# SCH_Quad_miner_2023-09-12.net
KiCad netlist of a schematic drawn in EasyEDA
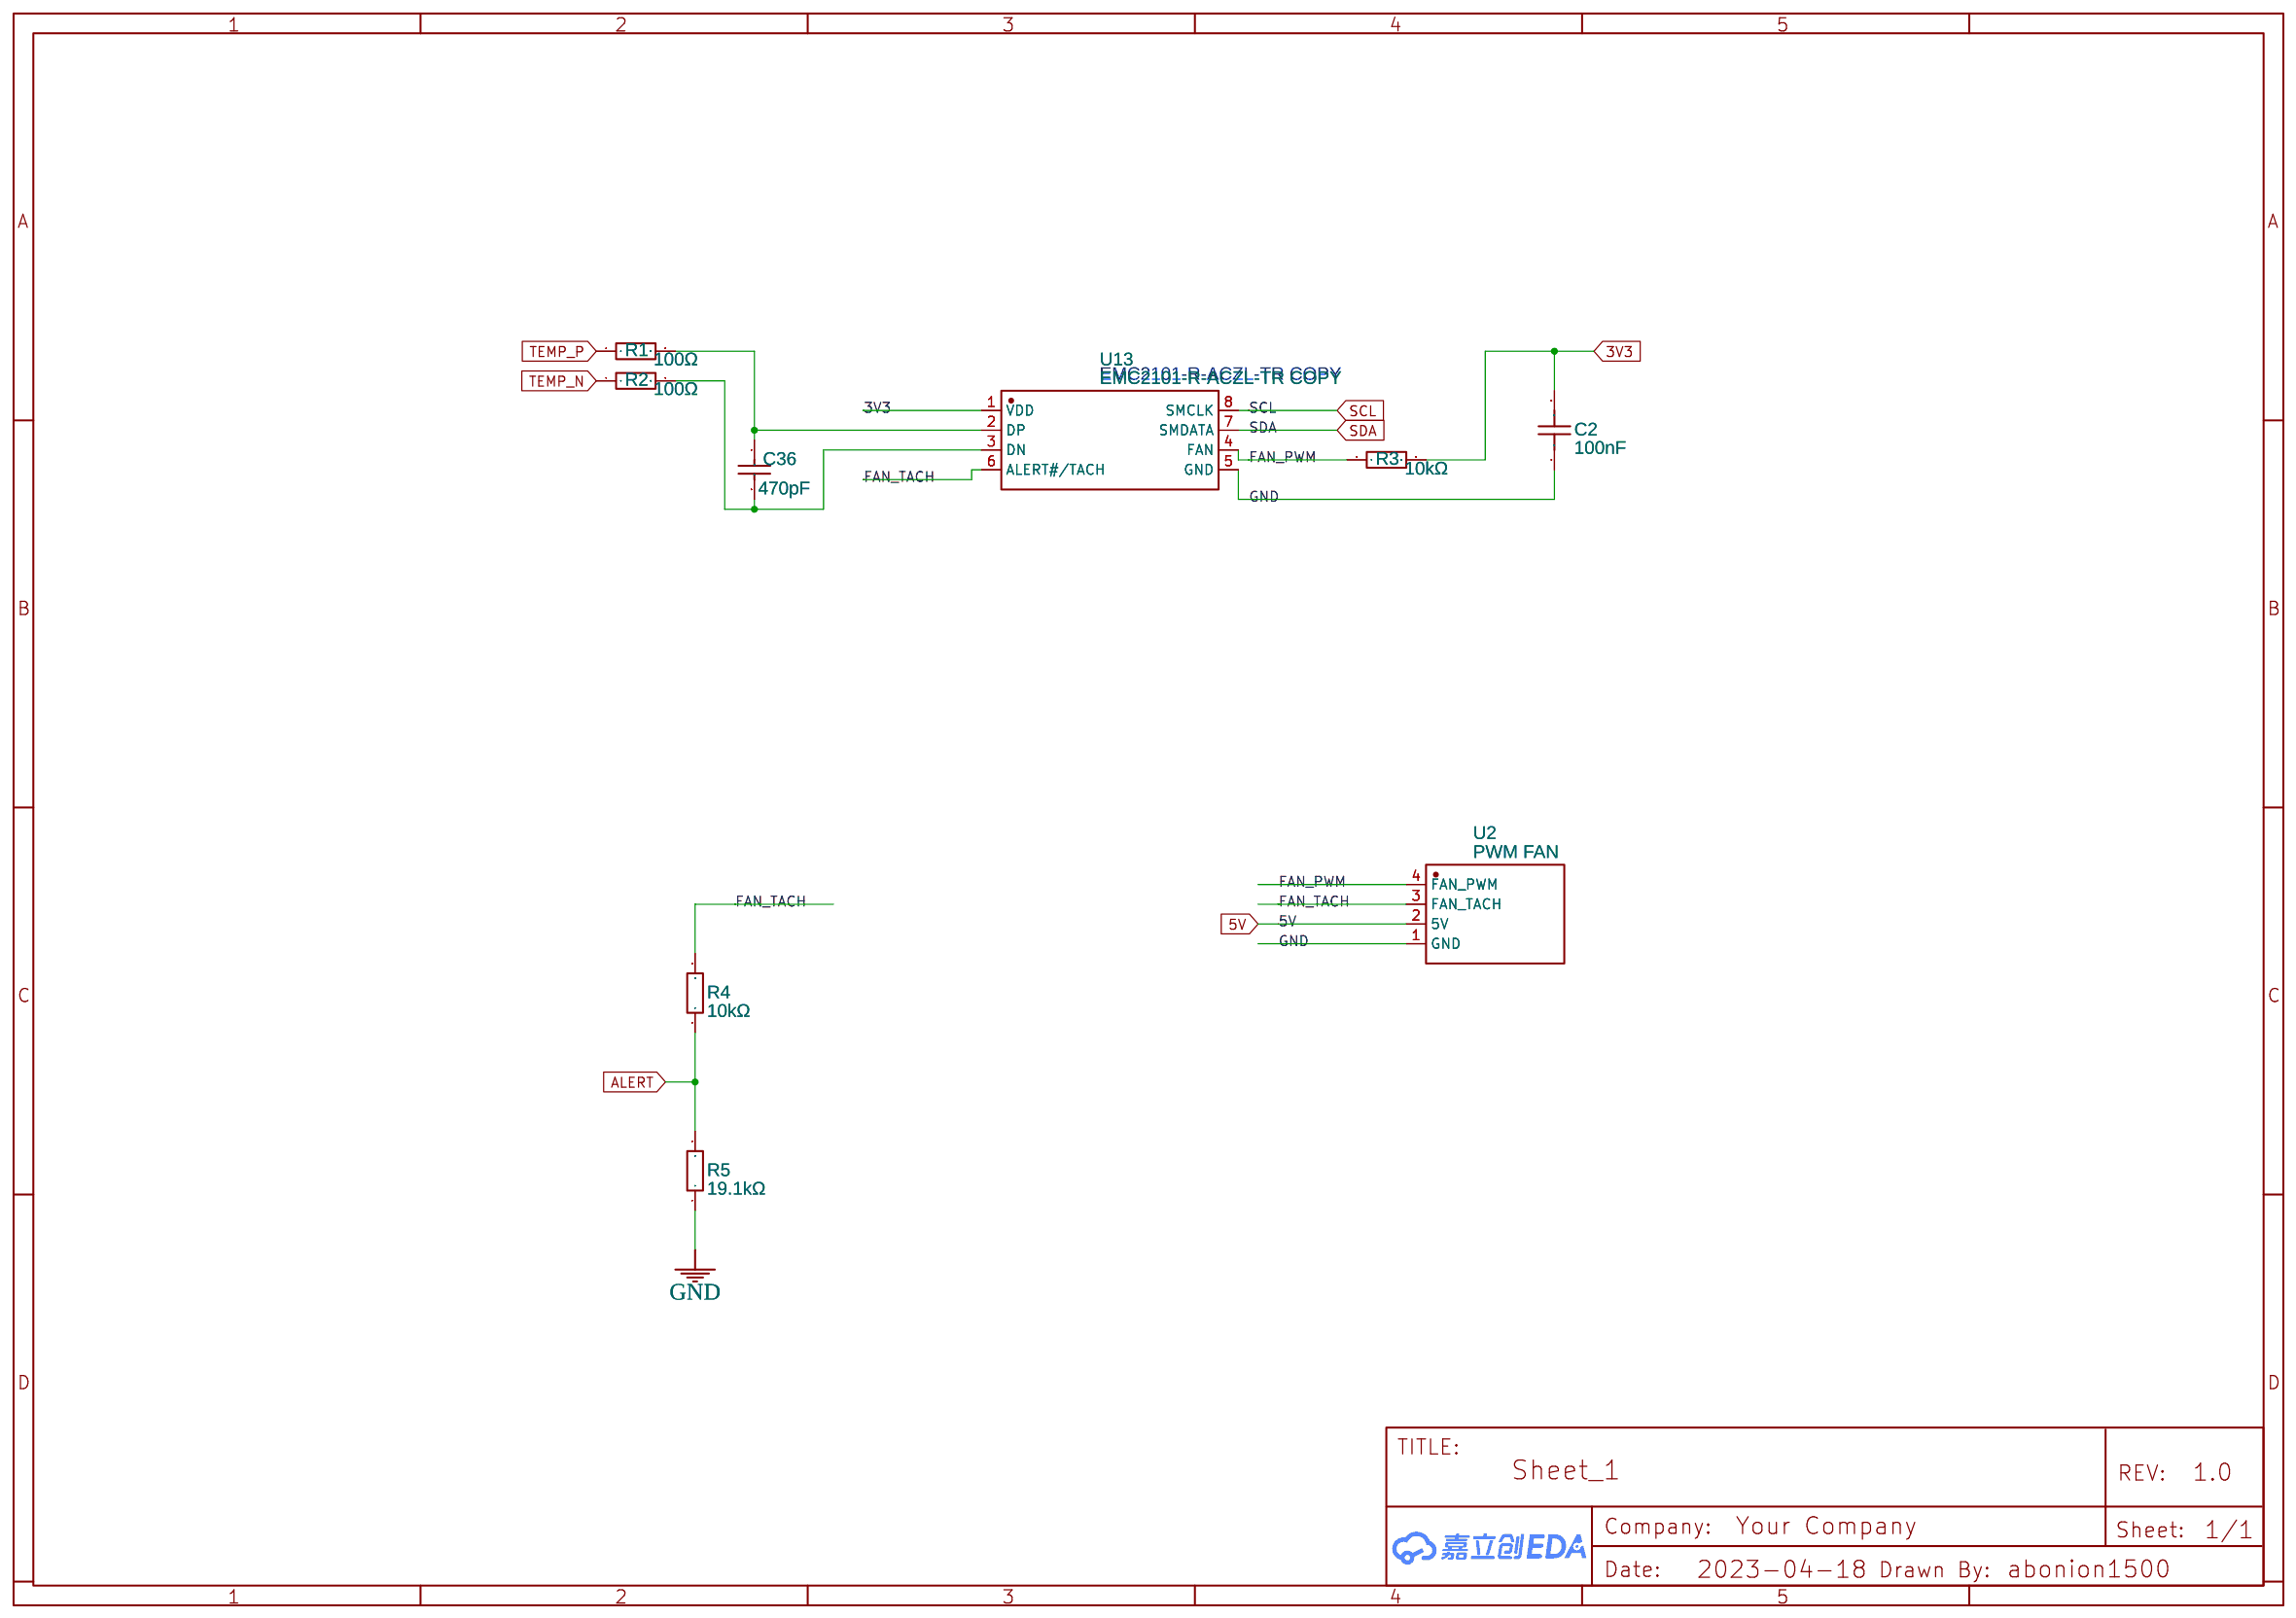
[diagram p0: EMC2101]
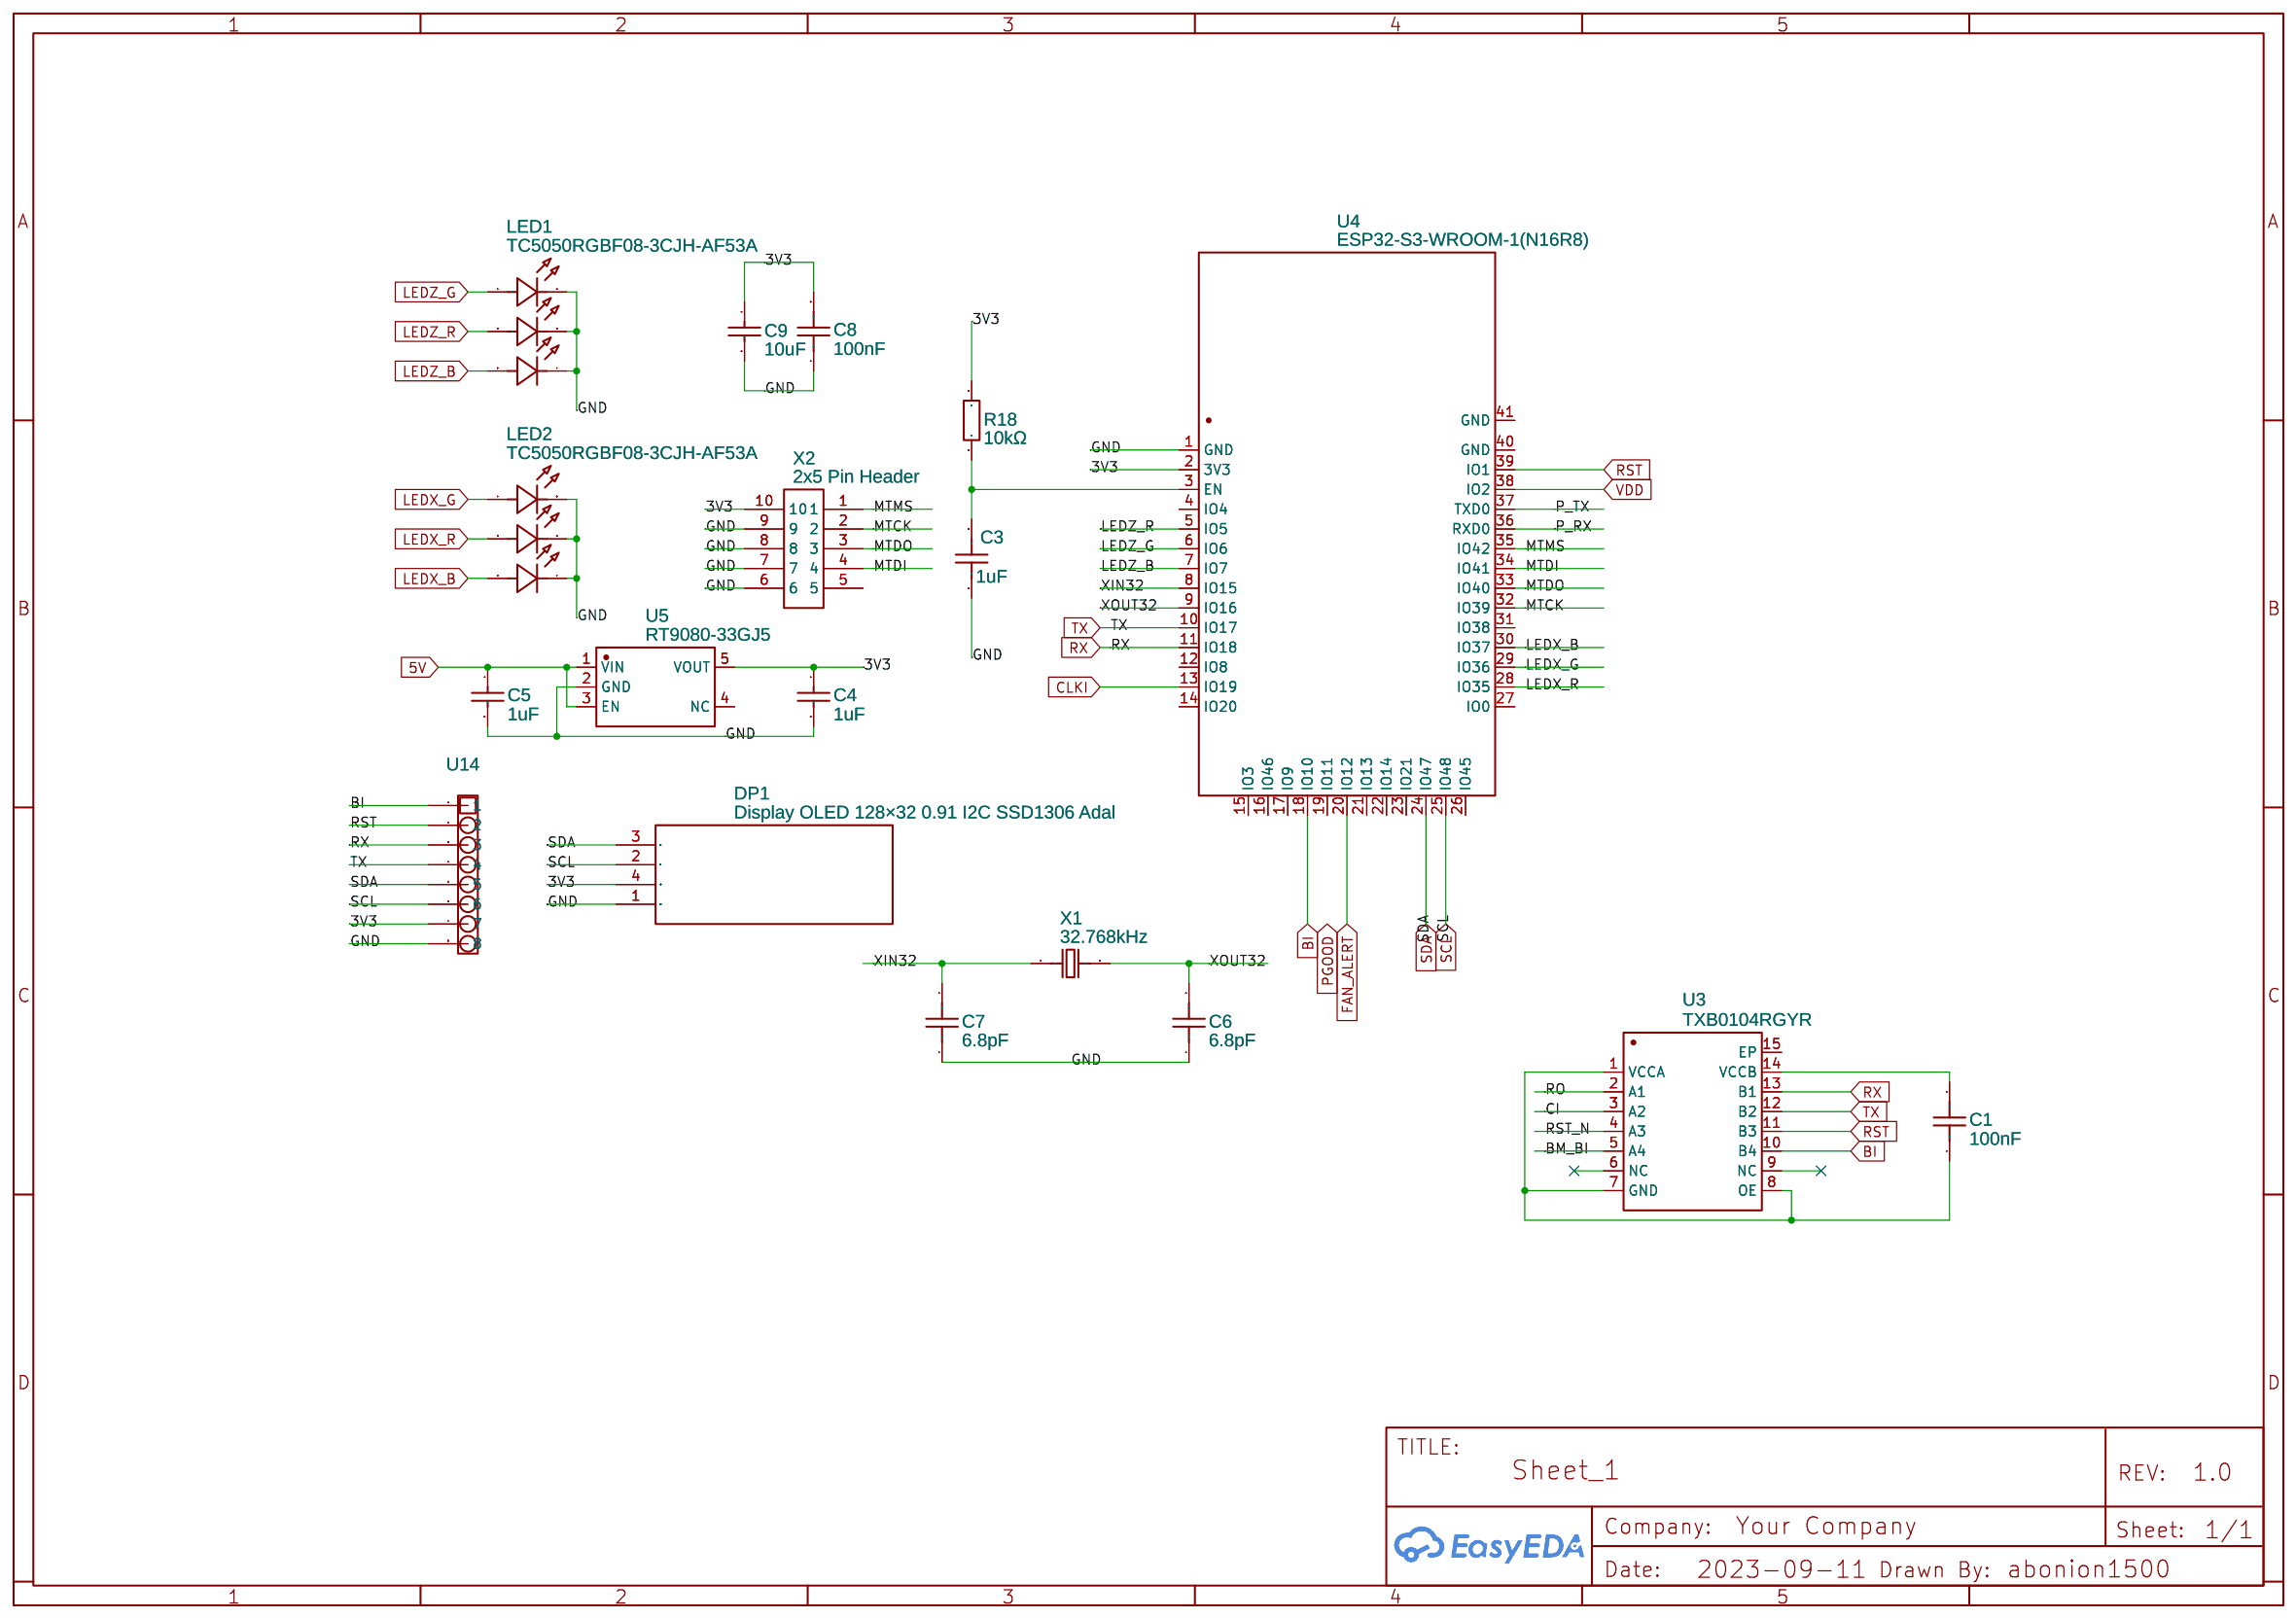
[diagram p1: Logic]
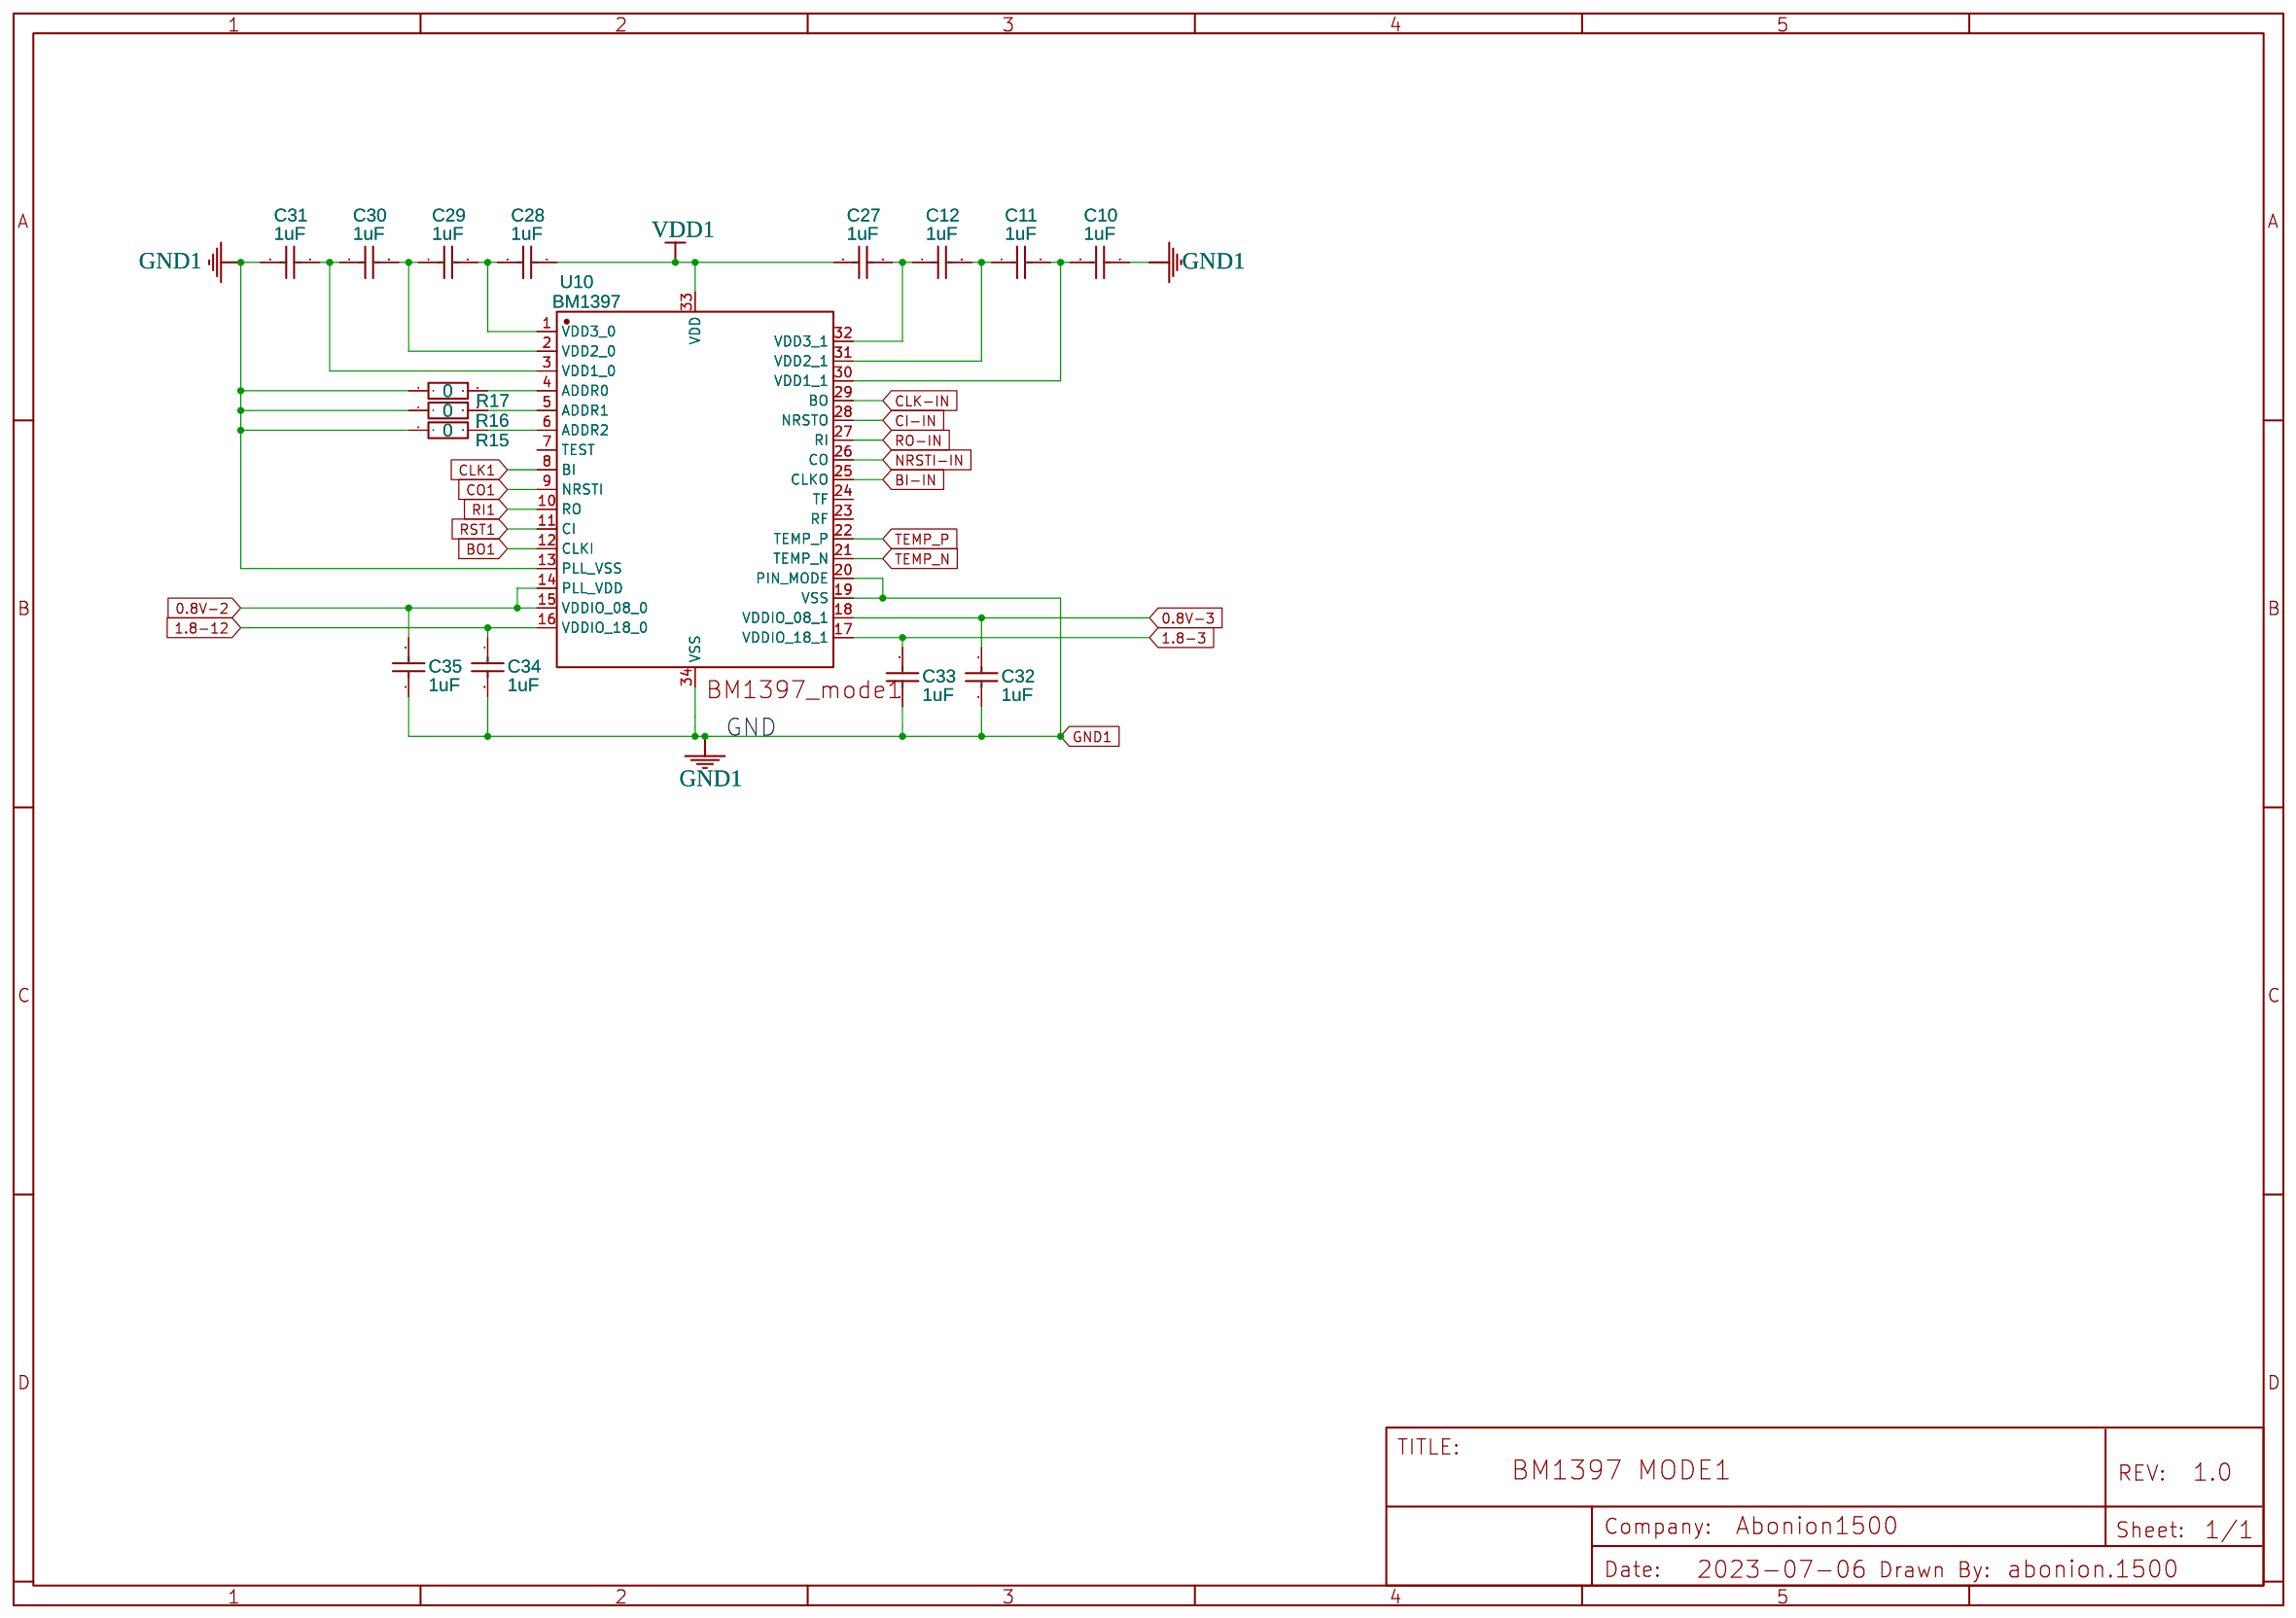
[diagram p2: Ic1]
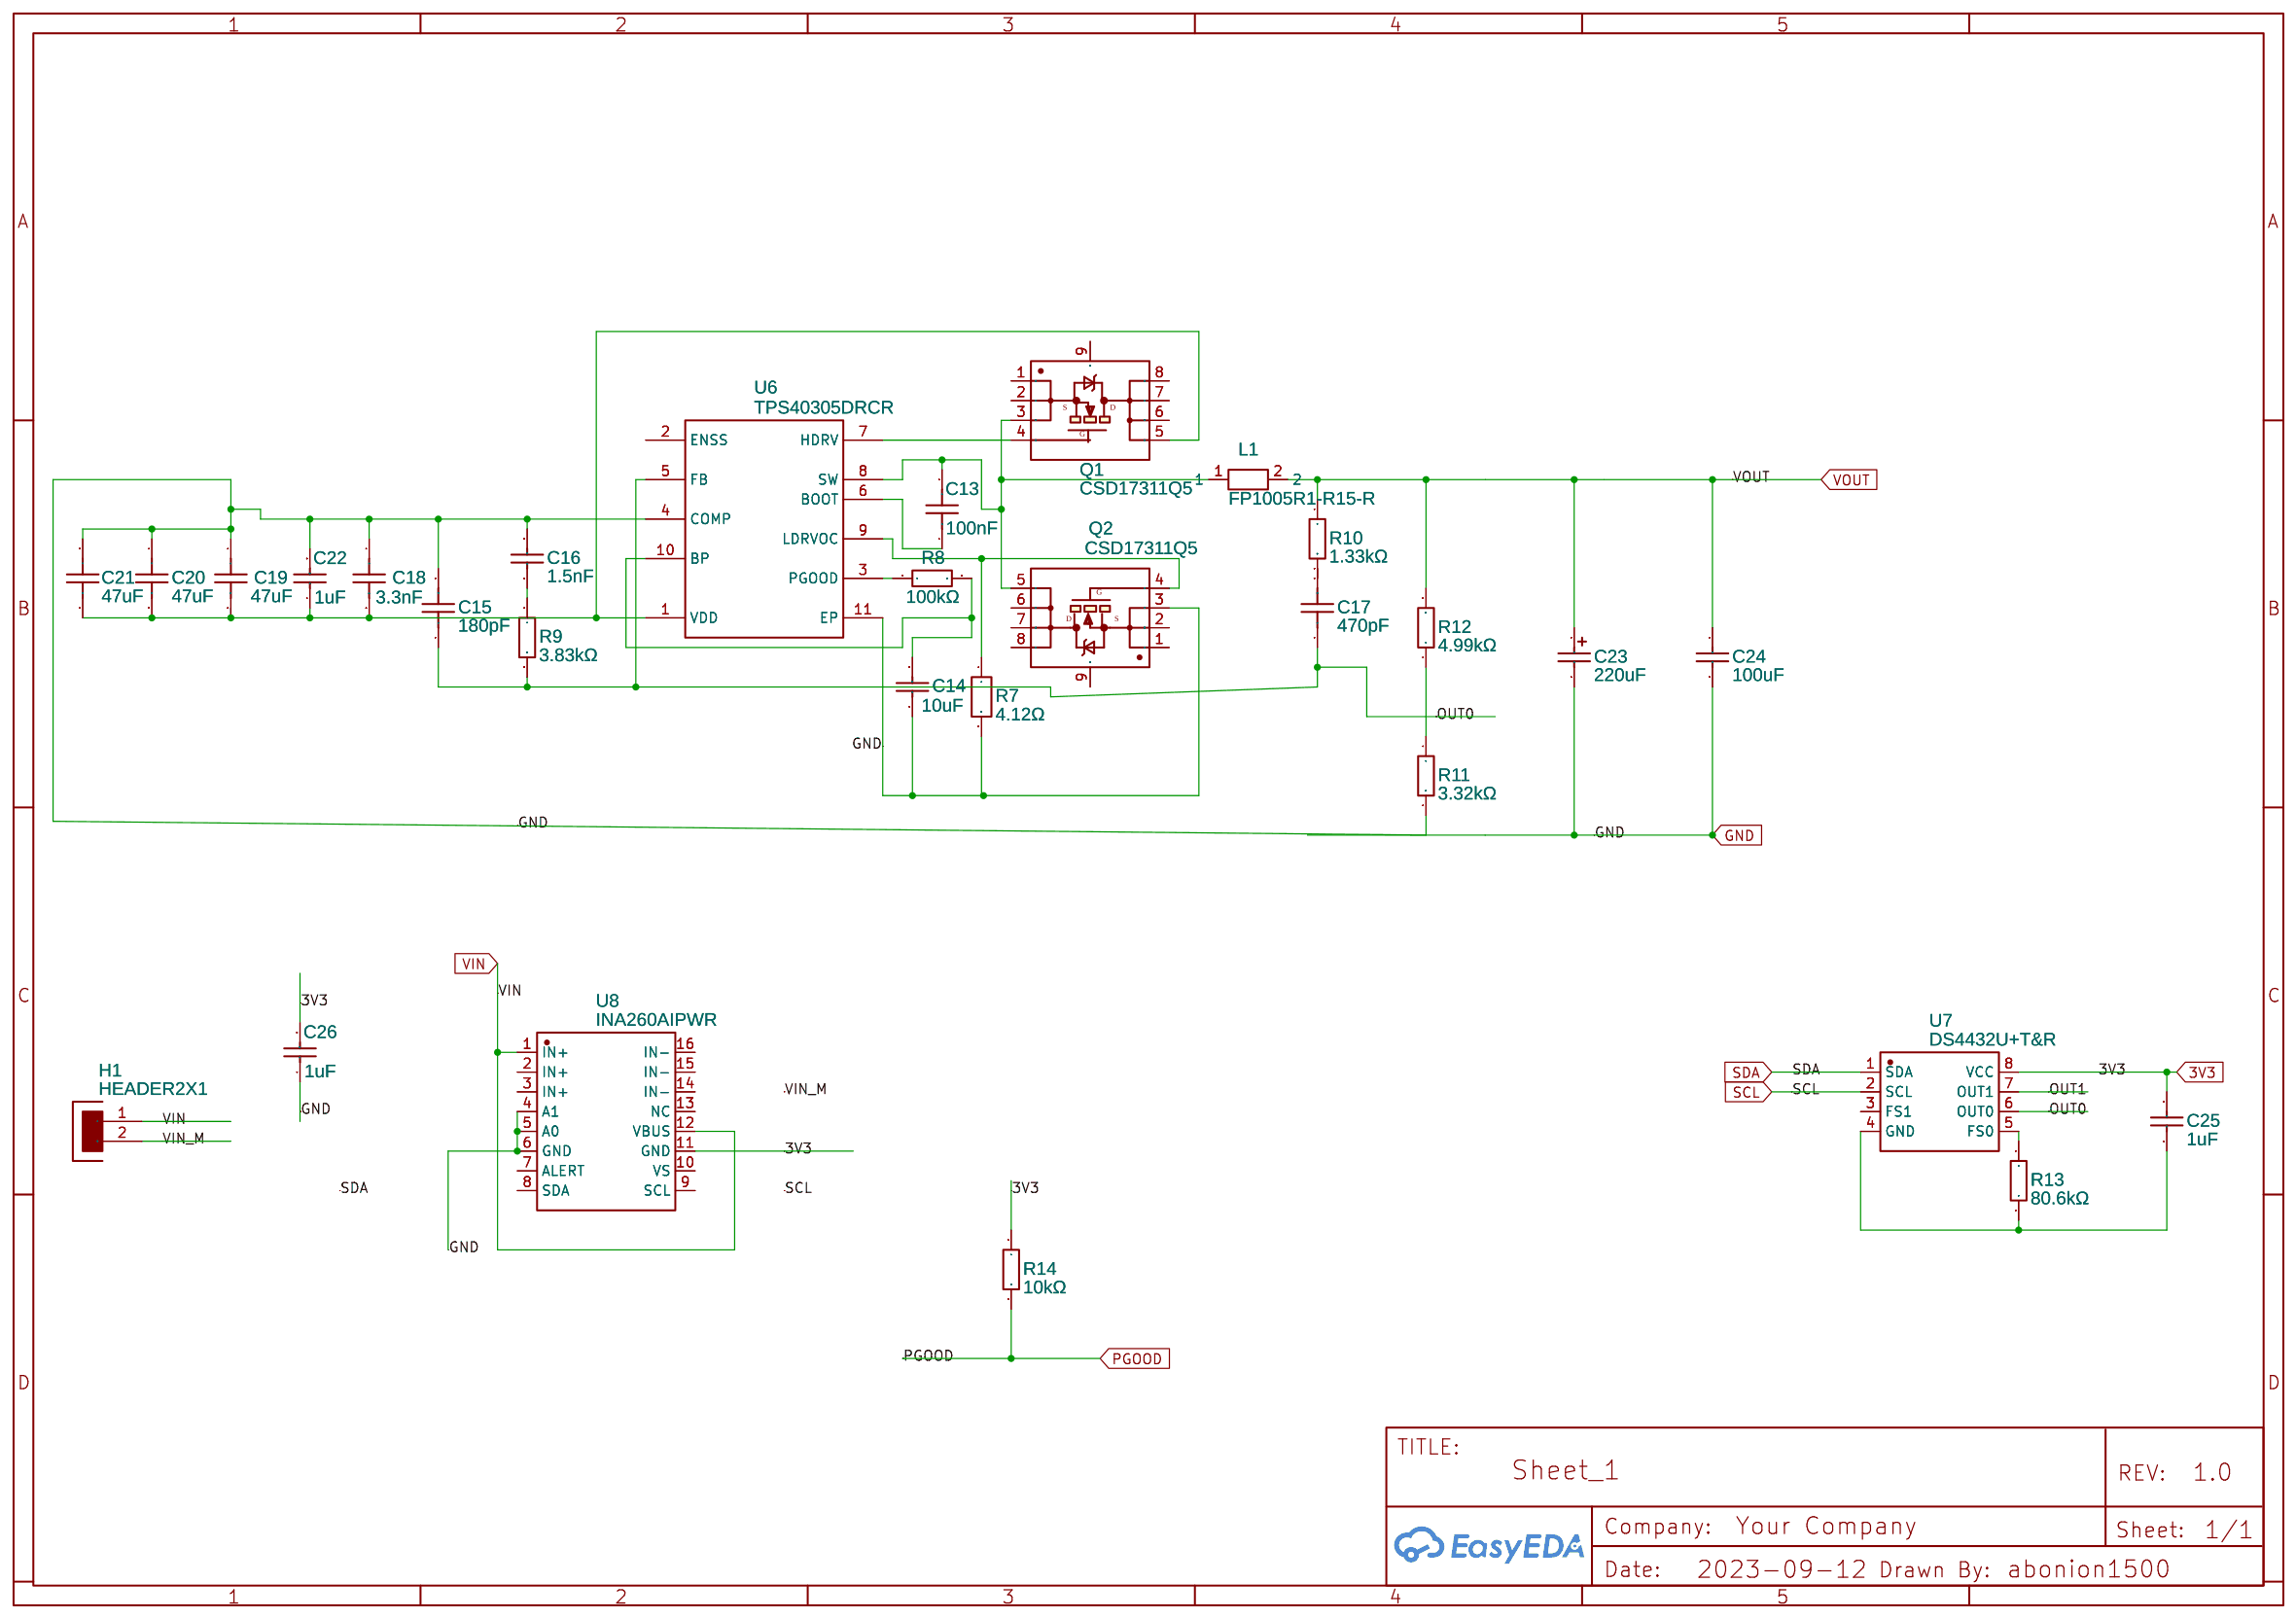
[diagram p3: Power main]
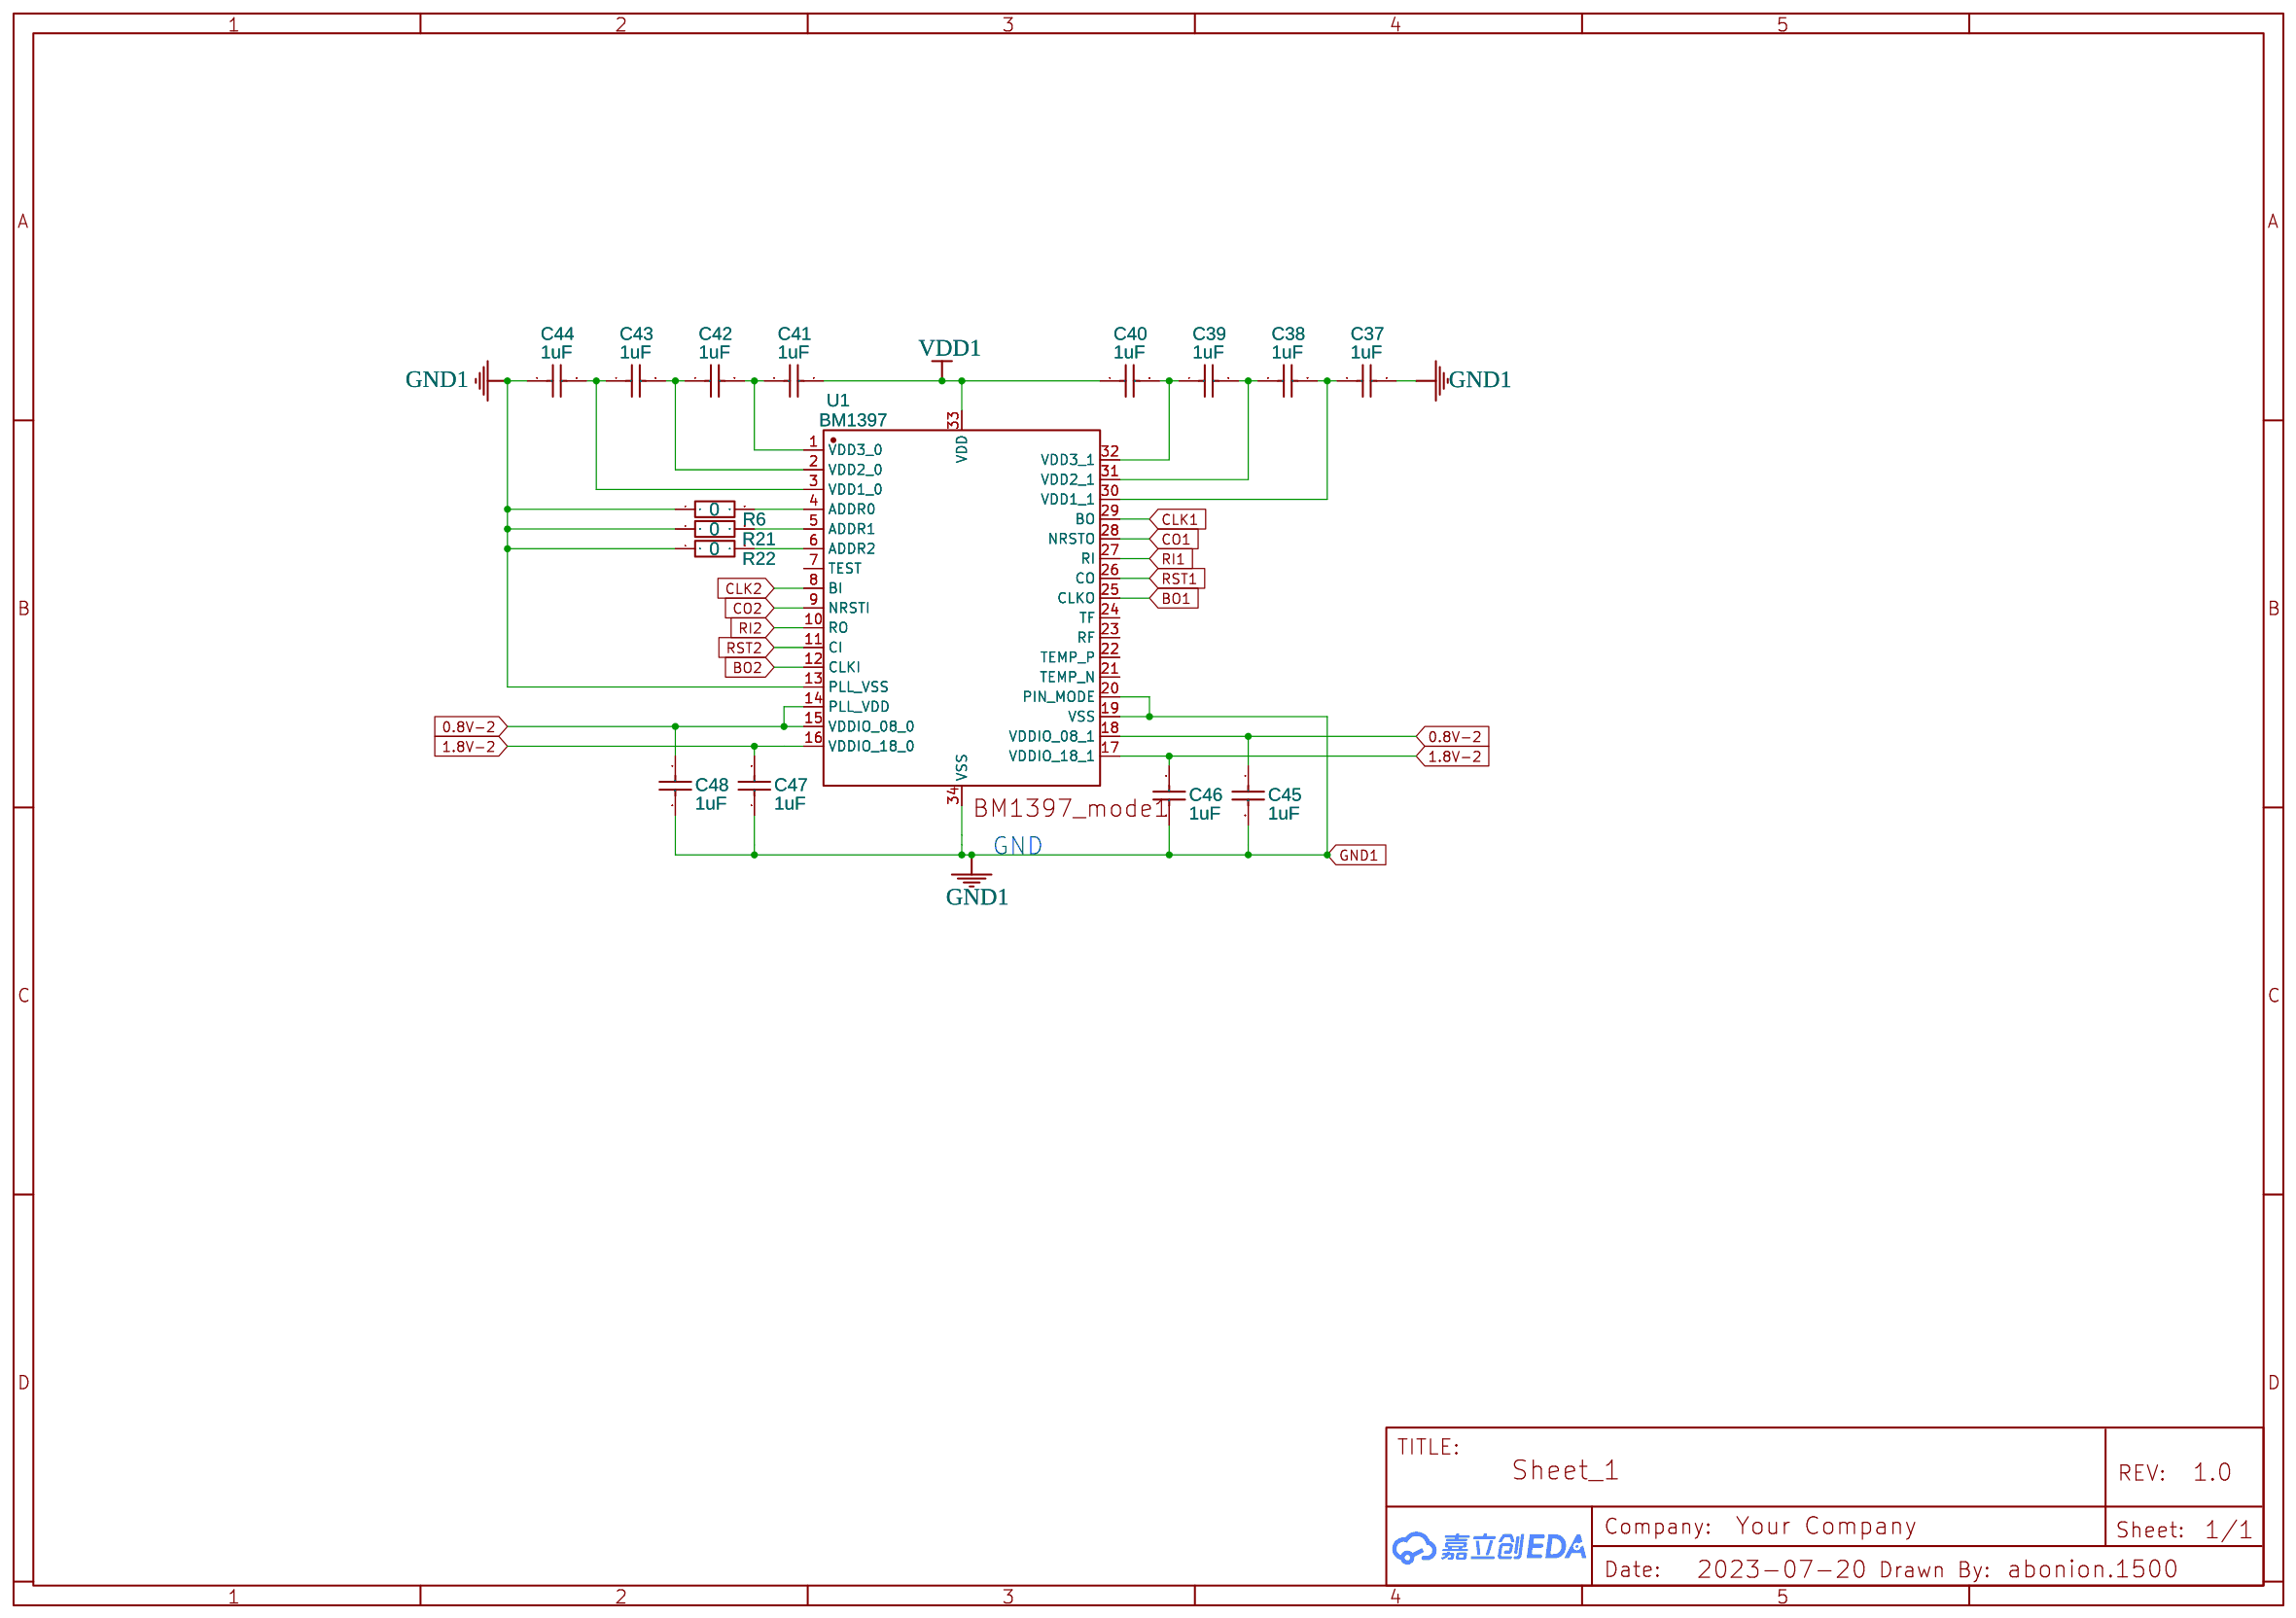
[diagram p4: Ic2]
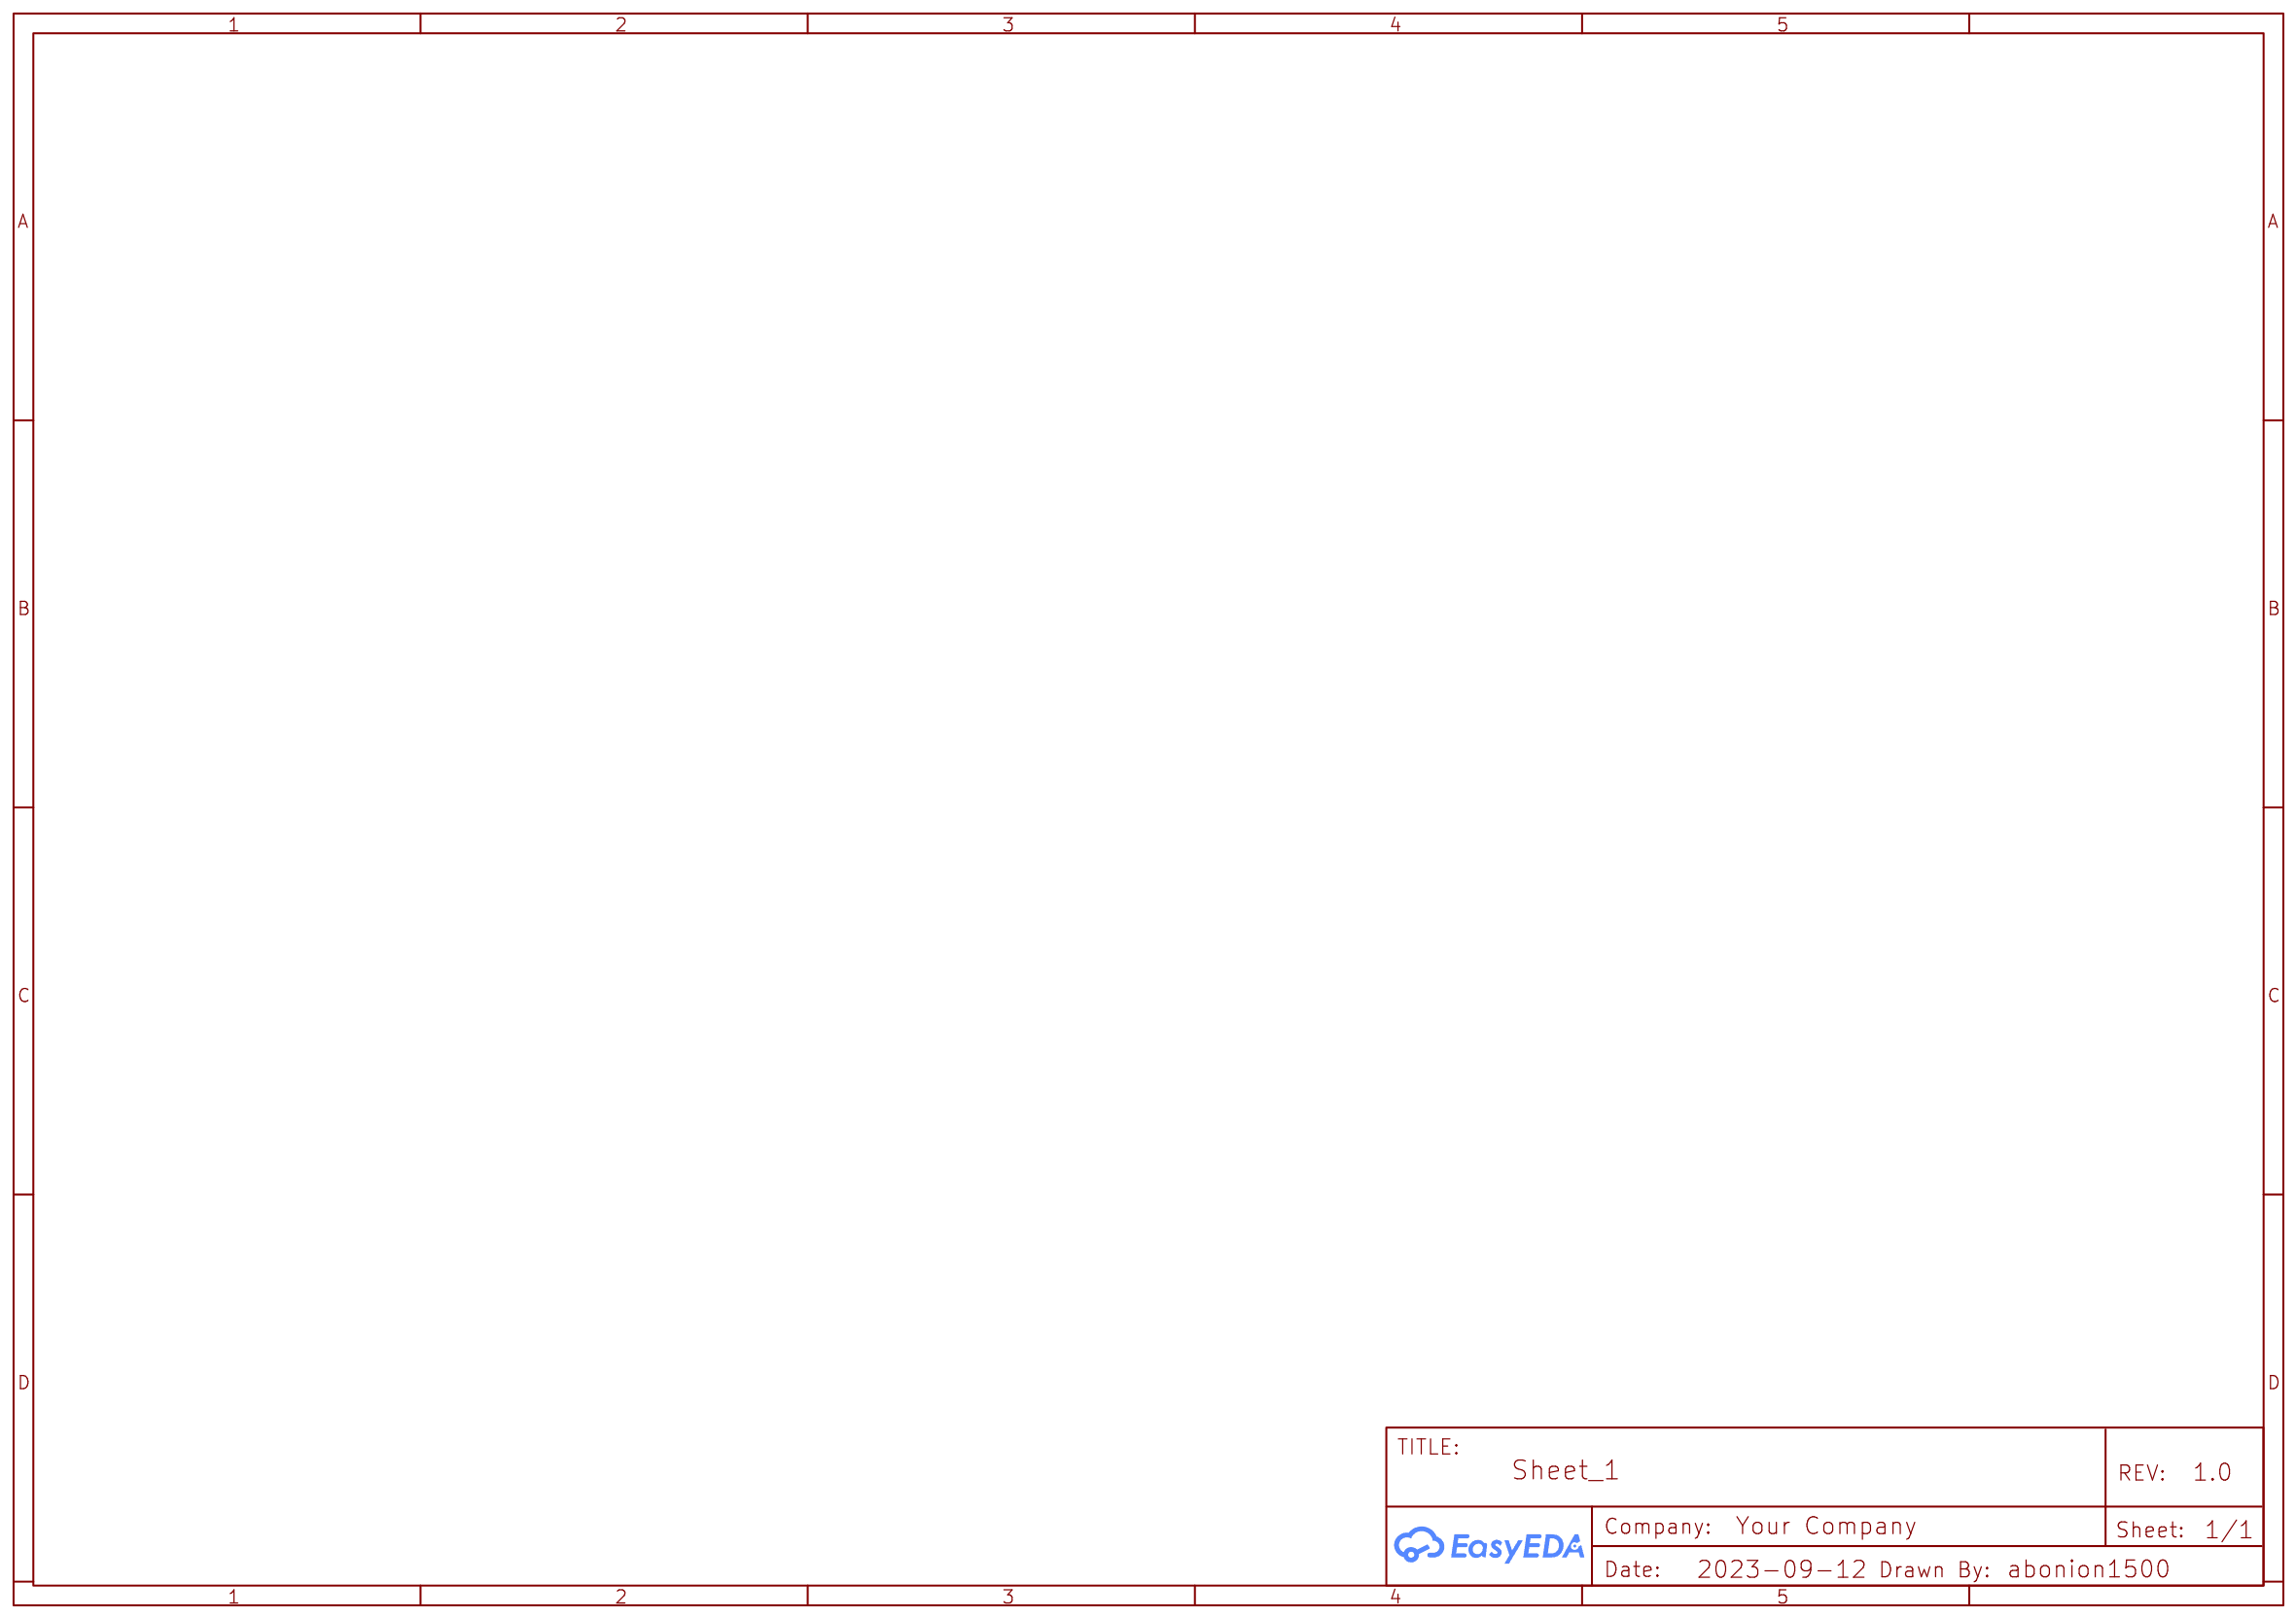
[diagram p5: Sheet_1]
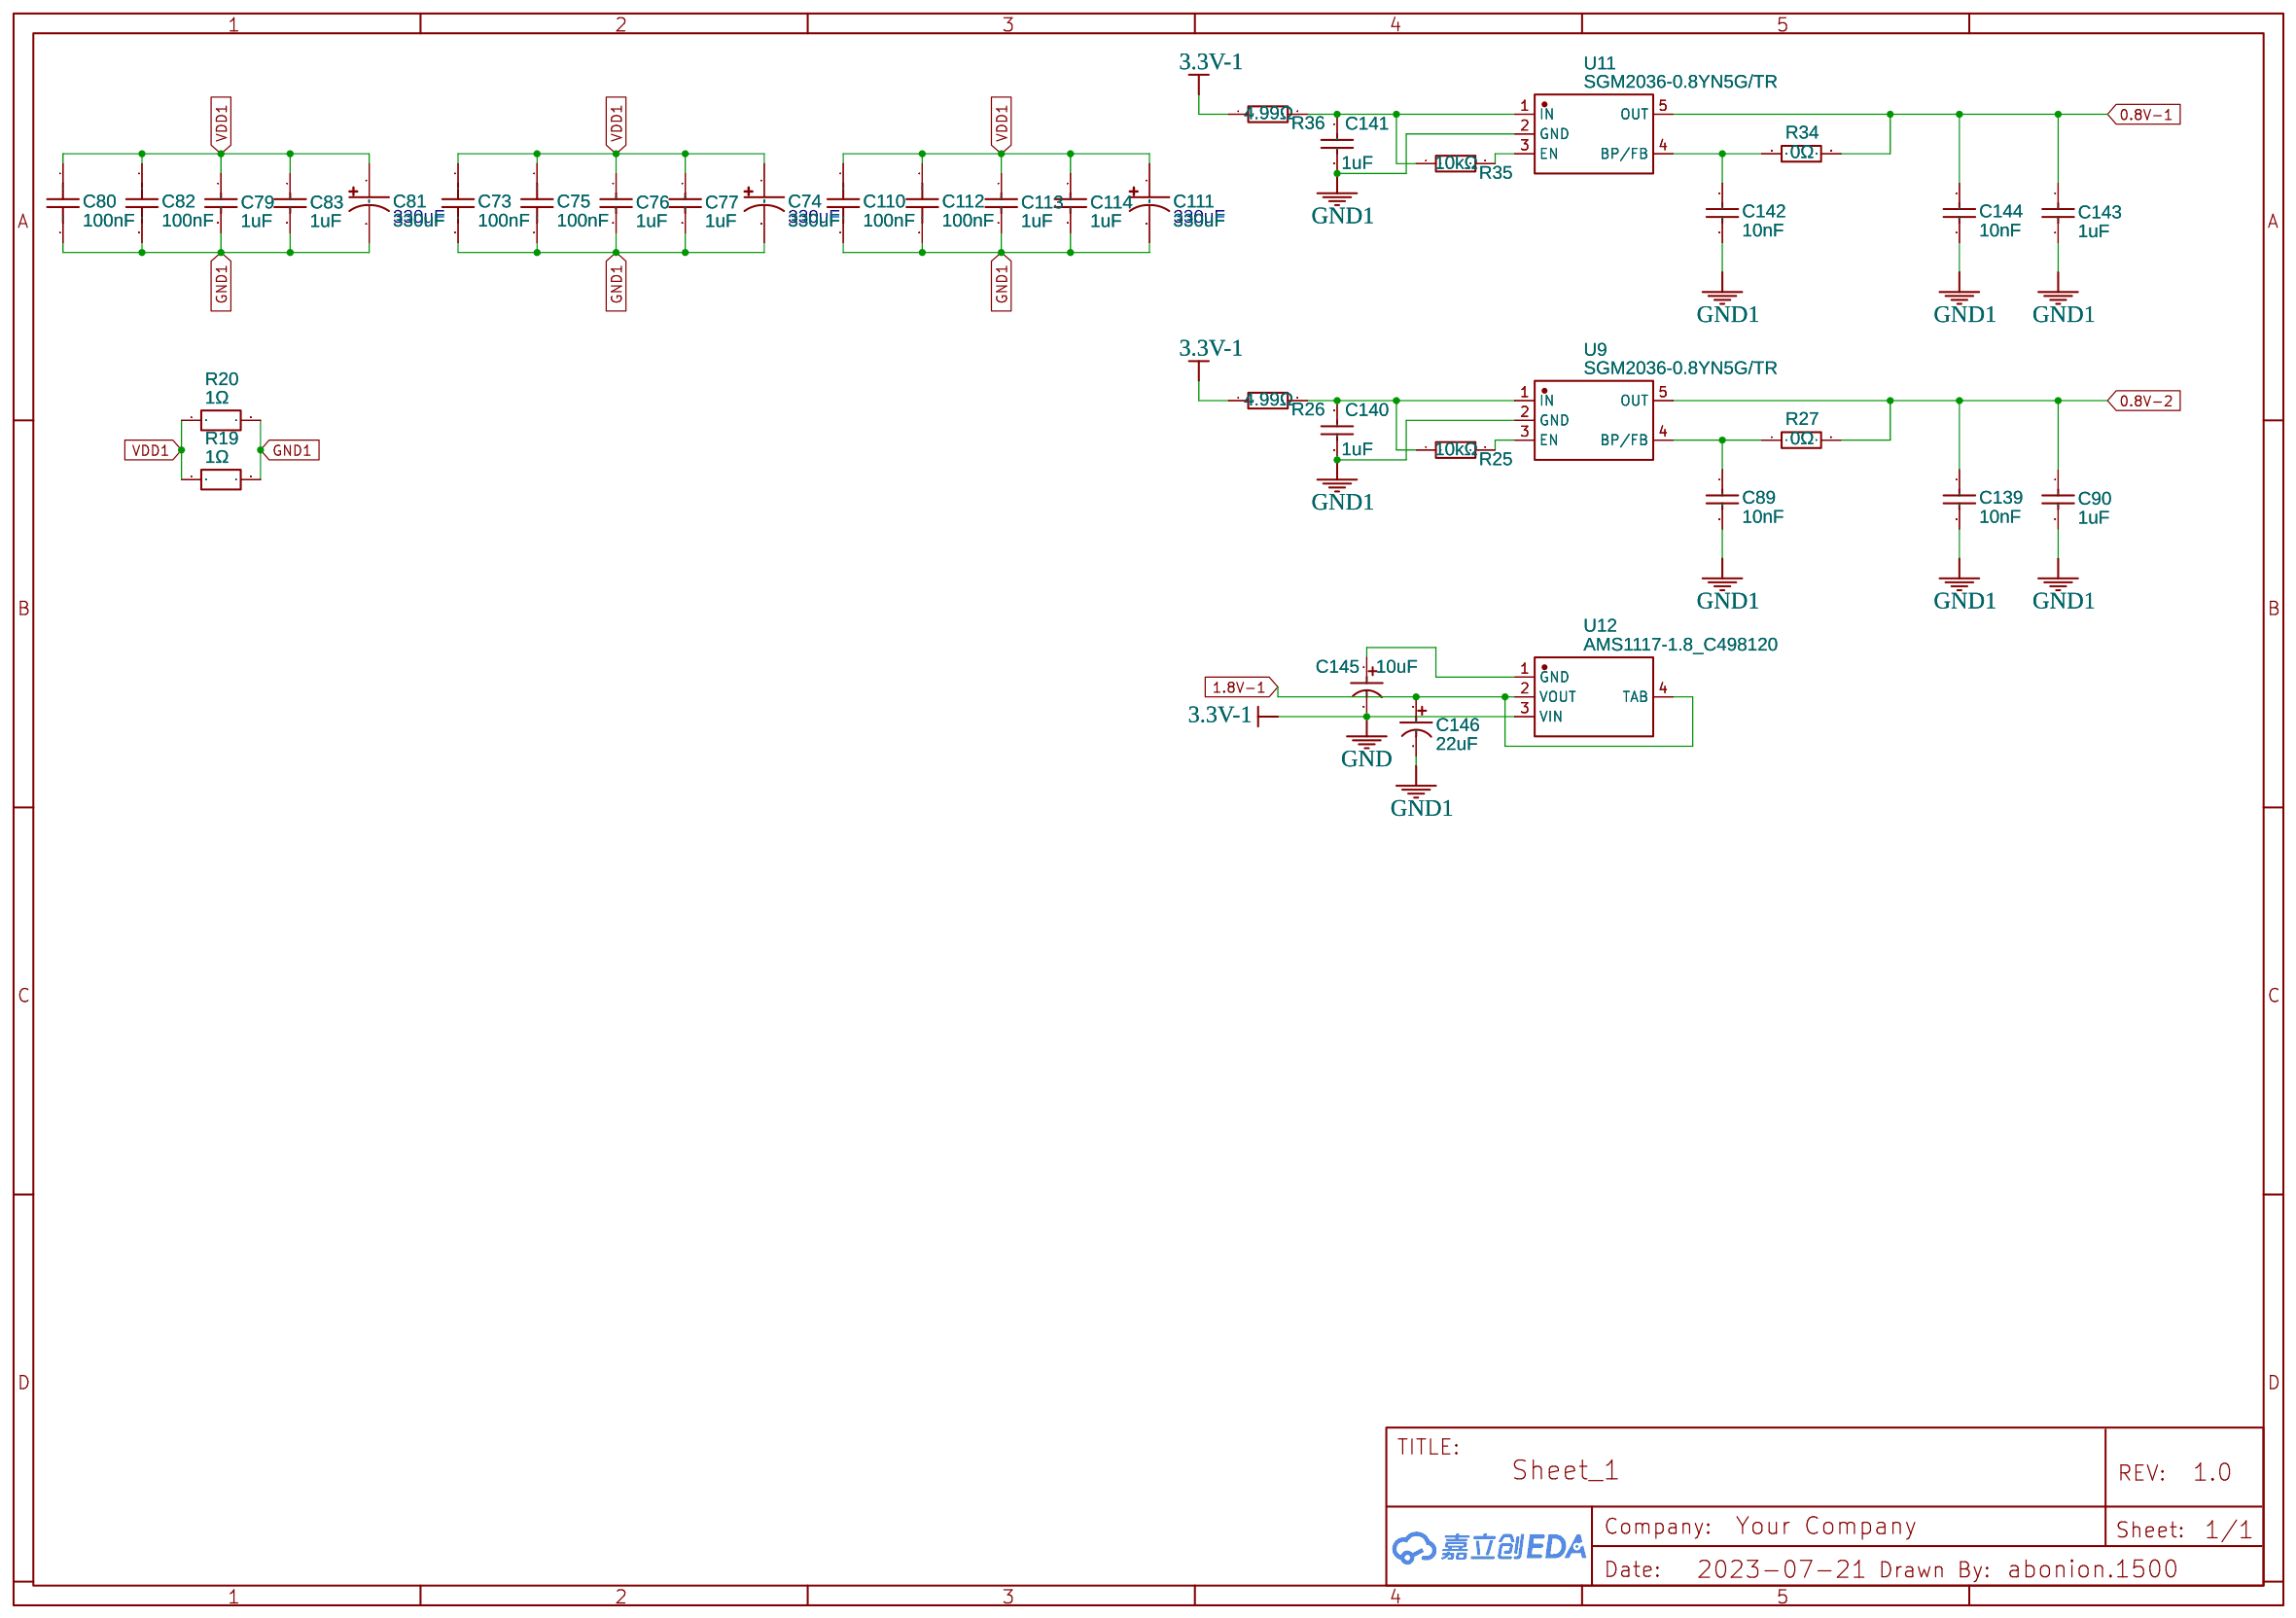
[diagram p6: Power ASICS]

(export (version "E")
  (design (tool "Eeschema 10.0.6"))
  (components
    (comp (ref "C2")
      (value "100nF")
      (fields (field (name "Manufacturer Part") "0402X104K100CT") (field (name "Manufacturer") "Walsin(华新科)"))
      (libsource (lib "") (part "0402X104K100CT"))
    )
    (comp (ref "C36")
      (value "470pF")
      (fields
        (field (name "Manufacturer Part") "CL05B471KB5NNNC")
        (field (name "Manufacturer") "SAMSUNG(三星)")
      )
      (libsource (lib "") (part "CL05B471KB5NNNC"))
    )
    (comp (ref "R1")
      (value "100Ω")
      (fields
        (field (name "Manufacturer Part") "RMCF0402FT100R")
        (field (name "Manufacturer") "SEI(Stackpole Electronics Inc.)")
      )
      (libsource (lib "") (part "RMCF0402FT100R"))
    )
    (comp (ref "R2")
      (value "100Ω")
      (fields
        (field (name "Manufacturer Part") "RMCF0402FT100R")
        (field (name "Manufacturer") "SEI(Stackpole Electronics Inc.)")
      )
      (libsource (lib "") (part "RMCF0402FT100R"))
    )
    (comp (ref "R3")
      (value "10kΩ")
      (fields (field (name "Manufacturer Part") "RC0402JR-0710KL") (field (name "Manufacturer") "YAGEO(国巨)"))
      (libsource (lib "") (part "RC0402JR-0710KL"))
    )
    (comp (ref "R4")
      (value "10kΩ")
      (fields (field (name "Manufacturer Part") "RC-02W103JT") (field (name "Manufacturer") "FH(风华)"))
      (libsource (lib "") (part "RC-02W103JT_C140214"))
    )
    (comp (ref "R5")
      (value "19.1kΩ")
      (fields
        (field (name "Manufacturer Part") "0402WGF1912TCE")
        (field (name "Manufacturer") "UNI-ROYAL(厚声)")
      )
      (libsource (lib "") (part "0402WGF1912TCE"))
    )
    (comp (ref "U2") (value "PWM FAN") (libsource (lib "") (part "PWM FAN")))
    (comp (ref "U13")
      (value "EMC2101-R-ACZL-TR COPY")
      (fields
        (field (name "Manufacturer Part") "EMC2101-R-ACZL-TR")
        (field (name "Manufacturer") "MICROCHIP(美国微芯)")
      )
      (libsource (lib "") (part "EMC2101-R-ACZL-TR COPY"))
    )
    (comp (ref "C1")
      (value "100nF")
      (fields (field (name "Manufacturer Part") "0402X104K100CT") (field (name "Manufacturer") "Walsin(华新科)"))
      (libsource (lib "") (part "0402X104K100CT"))
    )
    (comp (ref "C3")
      (value "1uF")
      (fields (field (name "Manufacturer Part") "0603X105J160CT") (field (name "Manufacturer") "Walsin(华新科)"))
      (libsource (lib "") (part "0603X105J160CT"))
    )
    (comp (ref "C4")
      (value "1uF")
      (fields
        (field (name "Manufacturer Part") "CL05A105KO5NNNC")
        (field (name "Manufacturer") "SAMSUNG(三星)")
      )
      (libsource (lib "") (part "CL05A105KO5NNNC"))
    )
    (comp (ref "C5")
      (value "1uF")
      (fields
        (field (name "Manufacturer Part") "CL05A105KO5NNNC")
        (field (name "Manufacturer") "SAMSUNG(三星)")
      )
      (libsource (lib "") (part "CL05A105KO5NNNC"))
    )
    (comp (ref "C6")
      (value "6.8pF")
      (fields (field (name "Manufacturer Part") "C1005NP0689DGT") (field (name "Manufacturer") "DARFON(达方)"))
      (libsource (lib "") (part "C1005NPO689DGT"))
    )
    (comp (ref "C7")
      (value "6.8pF")
      (fields (field (name "Manufacturer Part") "C1005NP0689DGT") (field (name "Manufacturer") "DARFON(达方)"))
      (libsource (lib "") (part "C1005NPO689DGT"))
    )
    (comp (ref "C8")
      (value "100nF")
      (fields (field (name "Manufacturer Part") "0402X104K100CT") (field (name "Manufacturer") "Walsin(华新科)"))
      (libsource (lib "") (part "0402X104K100CT"))
    )
    (comp (ref "C9")
      (value "10uF")
      (fields
        (field (name "Manufacturer Part") "CL21A106KOQNNNE")
        (field (name "Manufacturer") "SAMSUNG(三星)")
      )
      (libsource (lib "") (part "CL21A106KOQNNNE"))
    )
    (comp (ref "DP1")
      (value "Display OLED 128×32 0.91 I2C SSD1306 Adal")
      (libsource (lib "") (part "Display OLED 128×32 0.91 I2C SSD1306 Adal"))
    )
    (comp (ref "LED1")
      (value "TC5050RGBF08-3CJH-AF53A")
      (fields (field (name "Manufacturer") "TCWIN(天成)"))
      (libsource (lib "") (part "TC5050RGBF08-3CJH-AF53A"))
    )
    (comp (ref "LED2")
      (value "TC5050RGBF08-3CJH-AF53A")
      (fields (field (name "Manufacturer") "TCWIN(天成)"))
      (libsource (lib "") (part "TC5050RGBF08-3CJH-AF53A"))
    )
    (comp (ref "R18")
      (value "10kΩ")
      (fields (field (name "Manufacturer Part") "RC0402JR-0710KL") (field (name "Manufacturer") "YAGEO(国巨)"))
      (libsource (lib "") (part "RC0402JR-0710KL"))
    )
    (comp (ref "U3")
      (value "TXB0104RGYR")
      (fields (field (name "Manufacturer") "TI(德州仪器)"))
      (libsource (lib "") (part "TXB0104RGYR"))
    )
    (comp (ref "U4")
      (value "ESP32-S3-WROOM-1(N16R8)")
      (fields
        (field (name "Manufacturer Part") "ESP32-S3-WROOM-1-N16R8")
        (field (name "Manufacturer") "ESPRESSIF(乐鑫)")
      )
      (libsource (lib "") (part "ESP32-S3-WROOM-1(N16R8)"))
    )
    (comp (ref "U5")
      (value "RT9080-33GJ5")
      (fields (field (name "Manufacturer") "RICHTEK(台湾立锜)"))
      (libsource (lib "") (part "RT9080-33GJ5"))
    )
    (comp (ref "U14") (value "NO") (libsource (lib "") (part "Header pins 1X08")))
    (comp (ref "X1")
      (value "32.768kHz")
      (fields (field (name "Manufacturer Part") "Q13FC1350000200") (field (name "Manufacturer") "EPSON(爱普生)"))
      (libsource (lib "") (part "Q13FC1350000200"))
    )
    (comp (ref "X2") (value "2x5 Pin Header") (libsource (lib "") (part "2x5 Pin Header")))
    (comp (ref "C10")
      (value "1uF")
      (fields
        (field (name "Manufacturer Part") "CL05A105KO5NNNC")
        (field (name "Manufacturer") "SAMSUNG(三星)")
      )
      (libsource (lib "") (part "CL05A105KO5NNNC"))
    )
    (comp (ref "C11")
      (value "1uF")
      (fields
        (field (name "Manufacturer Part") "CL05A105KO5NNNC")
        (field (name "Manufacturer") "SAMSUNG(三星)")
      )
      (libsource (lib "") (part "CL05A105KO5NNNC"))
    )
    (comp (ref "C12")
      (value "1uF")
      (fields
        (field (name "Manufacturer Part") "CL05A105KO5NNNC")
        (field (name "Manufacturer") "SAMSUNG(三星)")
      )
      (libsource (lib "") (part "CL05A105KO5NNNC"))
    )
    (comp (ref "C27")
      (value "1uF")
      (fields
        (field (name "Manufacturer Part") "CL05A105KO5NNNC")
        (field (name "Manufacturer") "SAMSUNG(三星)")
      )
      (libsource (lib "") (part "CL05A105KO5NNNC"))
    )
    (comp (ref "C28")
      (value "1uF")
      (fields
        (field (name "Manufacturer Part") "CL05A105KO5NNNC")
        (field (name "Manufacturer") "SAMSUNG(三星)")
      )
      (libsource (lib "") (part "CL05A105KO5NNNC"))
    )
    (comp (ref "C29")
      (value "1uF")
      (fields
        (field (name "Manufacturer Part") "CL05A105KO5NNNC")
        (field (name "Manufacturer") "SAMSUNG(三星)")
      )
      (libsource (lib "") (part "CL05A105KO5NNNC"))
    )
    (comp (ref "C30")
      (value "1uF")
      (fields
        (field (name "Manufacturer Part") "CL05A105KO5NNNC")
        (field (name "Manufacturer") "SAMSUNG(三星)")
      )
      (libsource (lib "") (part "CL05A105KO5NNNC"))
    )
    (comp (ref "C31")
      (value "1uF")
      (fields
        (field (name "Manufacturer Part") "CL05A105KO5NNNC")
        (field (name "Manufacturer") "SAMSUNG(三星)")
      )
      (libsource (lib "") (part "CL05A105KO5NNNC"))
    )
    (comp (ref "C32")
      (value "1uF")
      (fields
        (field (name "Manufacturer Part") "CL05A105KO5NNNC")
        (field (name "Manufacturer") "SAMSUNG(三星)")
      )
      (libsource (lib "") (part "CL05A105KO5NNNC_1"))
    )
    (comp (ref "C33")
      (value "1uF")
      (fields
        (field (name "Manufacturer Part") "CL05A105KO5NNNC")
        (field (name "Manufacturer") "SAMSUNG(三星)")
      )
      (libsource (lib "") (part "CL05A105KO5NNNC_1"))
    )
    (comp (ref "C34")
      (value "1uF")
      (fields
        (field (name "Manufacturer Part") "CL05A105KO5NNNC")
        (field (name "Manufacturer") "SAMSUNG(三星)")
      )
      (libsource (lib "") (part "CL05A105KO5NNNC_1"))
    )
    (comp (ref "C35")
      (value "1uF")
      (fields
        (field (name "Manufacturer Part") "CL05A105KO5NNNC")
        (field (name "Manufacturer") "SAMSUNG(三星)")
      )
      (libsource (lib "") (part "CL05A105KO5NNNC_1"))
    )
    (comp (ref "R15")
      (value "0")
      (fields (field (name "Manufacturer Part") "RC0402JR-070RL") (field (name "Manufacturer") "YAGEO(国巨)"))
      (libsource (lib "") (part "RC0402JR-070RL"))
    )
    (comp (ref "R16")
      (value "0")
      (fields (field (name "Manufacturer Part") "RC0402JR-070RL") (field (name "Manufacturer") "YAGEO(国巨)"))
      (libsource (lib "") (part "RC0402JR-070RL"))
    )
    (comp (ref "R17")
      (value "0")
      (fields (field (name "Manufacturer Part") "RC0402JR-070RL") (field (name "Manufacturer") "YAGEO(国巨)"))
      (libsource (lib "") (part "RC0402JR-070RL"))
    )
    (comp (ref "U10")
      (value "BM1397")
      (fields (field (name "Manufacturer") "Bitmain"))
      (libsource (lib "") (part "BM1397"))
    )
    (comp (ref "C13")
      (value "100nF")
      (fields (field (name "Manufacturer Part") "0402X104K100CT") (field (name "Manufacturer") "Walsin(华新科)"))
      (libsource (lib "") (part "0402X104K100CT"))
    )
    (comp (ref "C14")
      (value "10uF")
      (fields
        (field (name "Manufacturer Part") "CL21A106KOQNNNE")
        (field (name "Manufacturer") "SAMSUNG(三星)")
      )
      (libsource (lib "") (part "CL21A106KOQNNNE"))
    )
    (comp (ref "C15")
      (value "180pF")
      (fields
        (field (name "Manufacturer Part") "CC0805JRNPO9BN181")
        (field (name "Manufacturer") "YAGEO(国巨)")
      )
      (libsource (lib "") (part "CC0805JRNPO9BN181"))
    )
    (comp (ref "C16")
      (value "1.5nF")
      (fields
        (field (name "Manufacturer Part") "CC0805KRX7R9BB152")
        (field (name "Manufacturer") "YAGEO(国巨)")
      )
      (libsource (lib "") (part "CC0805KRX7R9BB152"))
    )
    (comp (ref "C17")
      (value "470pF")
      (fields (field (name "Manufacturer Part") "0805B471K500CT") (field (name "Manufacturer") "Walsin(华新科)"))
      (libsource (lib "") (part "0805B471K500CT"))
    )
    (comp (ref "C18")
      (value "3.3nF")
      (fields
        (field (name "Manufacturer Part") "CL05B332KB5NNNC")
        (field (name "Manufacturer") "SAMSUNG(三星)")
      )
      (libsource (lib "") (part "CL05B332KB5NNNC"))
    )
    (comp (ref "C19")
      (value "47uF")
      (fields
        (field (name "Manufacturer Part") "GRM32ER61C476KE15L")
        (field (name "Manufacturer") "muRata(村田)")
      )
      (libsource (lib "") (part "GRM32ER61C476KE15L"))
    )
    (comp (ref "C20")
      (value "47uF")
      (fields
        (field (name "Manufacturer Part") "GRM32ER61C476KE15L")
        (field (name "Manufacturer") "muRata(村田)")
      )
      (libsource (lib "") (part "GRM32ER61C476KE15L"))
    )
    (comp (ref "C21")
      (value "47uF")
      (fields
        (field (name "Manufacturer Part") "GRM32ER61C476KE15L")
        (field (name "Manufacturer") "muRata(村田)")
      )
      (libsource (lib "") (part "GRM32ER61C476KE15L_1"))
    )
    (comp (ref "C22")
      (value "1uF")
      (fields
        (field (name "Manufacturer Part") "CL10A105KO8NNNC")
        (field (name "Manufacturer") "SAMSUNG(三星)")
      )
      (libsource (lib "") (part "CL10A105KO8NNNC"))
    )
    (comp (ref "C23")
      (value "220uF")
      (fields (field (name "Manufacturer Part") "2R5TPE220MF") (field (name "Manufacturer") "PANASONIC(松下)"))
      (libsource (lib "") (part "2R5TPE220MF"))
    )
    (comp (ref "C24")
      (value "100uF")
      (fields
        (field (name "Manufacturer Part") "CL31A107MQHNNNE")
        (field (name "Manufacturer") "SAMSUNG(三星)")
      )
      (libsource (lib "") (part "CL31A107MQHNNNE"))
    )
    (comp (ref "C25")
      (value "1uF")
      (fields
        (field (name "Manufacturer Part") "CL05A105KO5NNNC")
        (field (name "Manufacturer") "SAMSUNG(三星)")
      )
      (libsource (lib "") (part "CL05A105KO5NNNC"))
    )
    (comp (ref "C26")
      (value "1uF")
      (fields
        (field (name "Manufacturer Part") "CL10A105KO8NNNC")
        (field (name "Manufacturer") "SAMSUNG(三星)")
      )
      (libsource (lib "") (part "CL10A105KO8NNNC"))
    )
    (comp (ref "H1")
      (value "HEADER2X1")
      (fields (field (name "Manufacturer Part") "n/a"))
      (libsource (lib "") (part "HEADER2X1"))
    )
    (comp (ref "L1") (value "FP1005R1-R15-R") (libsource (lib "") (part "FP1005R1-R15-R")))
    (comp (ref "Q1")
      (value "CSD17311Q5")
      (fields (field (name "Manufacturer") "TI(德州仪器)"))
      (libsource (lib "") (part "CSD17311Q5_1"))
    )
    (comp (ref "Q2")
      (value "CSD17311Q5")
      (fields (field (name "Manufacturer") "TI(德州仪器)"))
      (libsource (lib "") (part "CSD17311Q5"))
    )
    (comp (ref "R7")
      (value "4.12Ω")
      (fields (field (name "Manufacturer Part") "RC0402FR-074R12L") (field (name "Manufacturer") "YAGEO(国巨)"))
      (libsource (lib "") (part "RC0402FR-074R12L"))
    )
    (comp (ref "R8")
      (value "100kΩ")
      (fields (field (name "Manufacturer Part") "RC0402JR-07100KL") (field (name "Manufacturer") "YAGEO(国巨)"))
      (libsource (lib "") (part "RC0402JR-07100KL"))
    )
    (comp (ref "R9")
      (value "3.83kΩ")
      (fields (field (name "Manufacturer Part") "RC0402FR-073K83L") (field (name "Manufacturer") "YAGEO(国巨)"))
      (libsource (lib "") (part "RC0402FR-073K83L"))
    )
    (comp (ref "R10")
      (value "1.33kΩ")
      (fields (field (name "Manufacturer Part") "RC0402FR-071K33L") (field (name "Manufacturer") "YAGEO(国巨)"))
      (libsource (lib "") (part "RC0402FR-071K33L"))
    )
    (comp (ref "R11")
      (value "3.32kΩ")
      (fields (field (name "Manufacturer Part") "RC0402FR-073K32L") (field (name "Manufacturer") "YAGEO(国巨)"))
      (libsource (lib "") (part "RC0402FR-073K32L"))
    )
    (comp (ref "R12")
      (value "4.99kΩ")
      (fields (field (name "Manufacturer Part") "RC0402FR-074K99L") (field (name "Manufacturer") "YAGEO(国巨)"))
      (libsource (lib "") (part "RC0402FR-074K99L"))
    )
    (comp (ref "R13")
      (value "80.6kΩ")
      (fields (field (name "Manufacturer Part") "RC0402FR-0780K6L") (field (name "Manufacturer") "YAGEO(国巨)"))
      (libsource (lib "") (part "RC0402FR-0780K6L"))
    )
    (comp (ref "R14")
      (value "10kΩ")
      (fields (field (name "Manufacturer Part") "RC0402JR-0710KL") (field (name "Manufacturer") "YAGEO(国巨)"))
      (libsource (lib "") (part "RC0402JR-0710KL"))
    )
    (comp (ref "U6")
      (value "TPS40305DRCR")
      (fields (field (name "Manufacturer") "TI(德州仪器)"))
      (libsource (lib "") (part "TPS40305DRCR"))
    )
    (comp (ref "U7")
      (value "DS4432U+T&R")
      (fields (field (name "Manufacturer") "ADI(亚德诺)/MAXIM(美信)"))
      (libsource (lib "") (part "DS4432U+T&amp;R"))
    )
    (comp (ref "U8")
      (value "INA260AIPWR")
      (fields (field (name "Manufacturer") "TI(德州仪器)"))
      (libsource (lib "") (part "INA260AIPWR"))
    )
    (comp (ref "C37")
      (value "1uF")
      (fields
        (field (name "Manufacturer Part") "CL05A105KO5NNNC")
        (field (name "Manufacturer") "SAMSUNG(三星)")
      )
      (libsource (lib "") (part "CL05A105KO5NNNC"))
    )
    (comp (ref "C38")
      (value "1uF")
      (fields
        (field (name "Manufacturer Part") "CL05A105KO5NNNC")
        (field (name "Manufacturer") "SAMSUNG(三星)")
      )
      (libsource (lib "") (part "CL05A105KO5NNNC"))
    )
    (comp (ref "C39")
      (value "1uF")
      (fields
        (field (name "Manufacturer Part") "CL05A105KO5NNNC")
        (field (name "Manufacturer") "SAMSUNG(三星)")
      )
      (libsource (lib "") (part "CL05A105KO5NNNC"))
    )
    (comp (ref "C40")
      (value "1uF")
      (fields
        (field (name "Manufacturer Part") "CL05A105KO5NNNC")
        (field (name "Manufacturer") "SAMSUNG(三星)")
      )
      (libsource (lib "") (part "CL05A105KO5NNNC"))
    )
    (comp (ref "C41")
      (value "1uF")
      (fields
        (field (name "Manufacturer Part") "CL05A105KO5NNNC")
        (field (name "Manufacturer") "SAMSUNG(三星)")
      )
      (libsource (lib "") (part "CL05A105KO5NNNC"))
    )
    (comp (ref "C42")
      (value "1uF")
      (fields
        (field (name "Manufacturer Part") "CL05A105KO5NNNC")
        (field (name "Manufacturer") "SAMSUNG(三星)")
      )
      (libsource (lib "") (part "CL05A105KO5NNNC"))
    )
    (comp (ref "C43")
      (value "1uF")
      (fields
        (field (name "Manufacturer Part") "CL05A105KO5NNNC")
        (field (name "Manufacturer") "SAMSUNG(三星)")
      )
      (libsource (lib "") (part "CL05A105KO5NNNC"))
    )
    (comp (ref "C44")
      (value "1uF")
      (fields
        (field (name "Manufacturer Part") "CL05A105KO5NNNC")
        (field (name "Manufacturer") "SAMSUNG(三星)")
      )
      (libsource (lib "") (part "CL05A105KO5NNNC"))
    )
    (comp (ref "C45")
      (value "1uF")
      (fields
        (field (name "Manufacturer Part") "CL05A105KO5NNNC")
        (field (name "Manufacturer") "SAMSUNG(三星)")
      )
      (libsource (lib "") (part "CL05A105KO5NNNC_1"))
    )
    (comp (ref "C46")
      (value "1uF")
      (fields
        (field (name "Manufacturer Part") "CL05A105KO5NNNC")
        (field (name "Manufacturer") "SAMSUNG(三星)")
      )
      (libsource (lib "") (part "CL05A105KO5NNNC_1"))
    )
    (comp (ref "C47")
      (value "1uF")
      (fields
        (field (name "Manufacturer Part") "CL05A105KO5NNNC")
        (field (name "Manufacturer") "SAMSUNG(三星)")
      )
      (libsource (lib "") (part "CL05A105KO5NNNC_1"))
    )
    (comp (ref "C48")
      (value "1uF")
      (fields
        (field (name "Manufacturer Part") "CL05A105KO5NNNC")
        (field (name "Manufacturer") "SAMSUNG(三星)")
      )
      (libsource (lib "") (part "CL05A105KO5NNNC_1"))
    )
    (comp (ref "R6")
      (value "0")
      (fields (field (name "Manufacturer Part") "RC0402JR-070RL") (field (name "Manufacturer") "YAGEO(国巨)"))
      (libsource (lib "") (part "RC0402JR-070RL"))
    )
    (comp (ref "R21")
      (value "0")
      (fields (field (name "Manufacturer Part") "RC0402JR-070RL") (field (name "Manufacturer") "YAGEO(国巨)"))
      (libsource (lib "") (part "RC0402JR-070RL"))
    )
    (comp (ref "R22")
      (value "0")
      (fields (field (name "Manufacturer Part") "RC0402JR-070RL") (field (name "Manufacturer") "YAGEO(国巨)"))
      (libsource (lib "") (part "RC0402JR-070RL"))
    )
    (comp (ref "U1")
      (value "BM1397")
      (fields (field (name "Manufacturer") "Bitmain"))
      (libsource (lib "") (part "BM1397"))
    )
    (comp (ref "C73")
      (value "100nF")
      (fields
        (field (name "Manufacturer Part") "CC0402KRX7R7BB104")
        (field (name "Manufacturer") "YAGEO(国巨)")
      )
      (libsource (lib "") (part "CC0402KRX7R7BB104"))
    )
    (comp (ref "C74")
      (value "330uF")
      (fields (field (name "Manufacturer Part") "RVE1C331M0810") (field (name "Manufacturer") "HONOR(荣誉)"))
      (libsource (lib "") (part "RVE1C331M0810"))
    )
    (comp (ref "C75")
      (value "100nF")
      (fields
        (field (name "Manufacturer Part") "CC0402KRX7R7BB104")
        (field (name "Manufacturer") "YAGEO(国巨)")
      )
      (libsource (lib "") (part "CC0402KRX7R7BB104"))
    )
    (comp (ref "C76")
      (value "1uF")
      (fields
        (field (name "Manufacturer Part") "CL05A105KO5NNNC")
        (field (name "Manufacturer") "SAMSUNG(三星)")
      )
      (libsource (lib "") (part "CL05A105KO5NNNC"))
    )
    (comp (ref "C77")
      (value "1uF")
      (fields
        (field (name "Manufacturer Part") "CL05A105KO5NNNC")
        (field (name "Manufacturer") "SAMSUNG(三星)")
      )
      (libsource (lib "") (part "CL05A105KO5NNNC"))
    )
    (comp (ref "C79")
      (value "1uF")
      (fields
        (field (name "Manufacturer Part") "CL05A105KO5NNNC")
        (field (name "Manufacturer") "SAMSUNG(三星)")
      )
      (libsource (lib "") (part "CL05A105KO5NNNC"))
    )
    (comp (ref "C80")
      (value "100nF")
      (fields
        (field (name "Manufacturer Part") "CC0402KRX7R7BB104")
        (field (name "Manufacturer") "YAGEO(国巨)")
      )
      (libsource (lib "") (part "CC0402KRX7R7BB104"))
    )
    (comp (ref "C81")
      (value "330uF")
      (fields (field (name "Manufacturer Part") "RVE1C331M0810") (field (name "Manufacturer") "HONOR(荣誉)"))
      (libsource (lib "") (part "RVE1C331M0810_1"))
    )
    (comp (ref "C82")
      (value "100nF")
      (fields
        (field (name "Manufacturer Part") "CC0402KRX7R7BB104")
        (field (name "Manufacturer") "YAGEO(国巨)")
      )
      (libsource (lib "") (part "CC0402KRX7R7BB104"))
    )
    (comp (ref "C83")
      (value "1uF")
      (fields
        (field (name "Manufacturer Part") "CL05A105KO5NNNC")
        (field (name "Manufacturer") "SAMSUNG(三星)")
      )
      (libsource (lib "") (part "CL05A105KO5NNNC"))
    )
    (comp (ref "C89")
      (value "10nF")
      (fields (field (name "Manufacturer Part") "0402B103K500NT") (field (name "Manufacturer") "FH(风华)"))
      (libsource (lib "") (part "0402B103K500NT"))
    )
    (comp (ref "C90")
      (value "1uF")
      (fields
        (field (name "Manufacturer Part") "CL05A105KO5NNNC")
        (field (name "Manufacturer") "SAMSUNG(三星)")
      )
      (libsource (lib "") (part "CL05A105KO5NNNC"))
    )
    (comp (ref "C110")
      (value "100nF")
      (fields
        (field (name "Manufacturer Part") "CC0402KRX7R7BB104")
        (field (name "Manufacturer") "YAGEO(国巨)")
      )
      (libsource (lib "") (part "CC0402KRX7R7BB104"))
    )
    (comp (ref "C111")
      (value "330uF")
      (fields (field (name "Manufacturer Part") "RVE1C331M0810") (field (name "Manufacturer") "HONOR(荣誉)"))
      (libsource (lib "") (part "RVE1C331M0810"))
    )
    (comp (ref "C112")
      (value "100nF")
      (fields
        (field (name "Manufacturer Part") "CC0402KRX7R7BB104")
        (field (name "Manufacturer") "YAGEO(国巨)")
      )
      (libsource (lib "") (part "CC0402KRX7R7BB104"))
    )
    (comp (ref "C113")
      (value "1uF")
      (fields
        (field (name "Manufacturer Part") "CL05A105KO5NNNC")
        (field (name "Manufacturer") "SAMSUNG(三星)")
      )
      (libsource (lib "") (part "CL05A105KO5NNNC"))
    )
    (comp (ref "C114")
      (value "1uF")
      (fields
        (field (name "Manufacturer Part") "CL05A105KO5NNNC")
        (field (name "Manufacturer") "SAMSUNG(三星)")
      )
      (libsource (lib "") (part "CL05A105KO5NNNC"))
    )
    (comp (ref "C139")
      (value "10nF")
      (fields (field (name "Manufacturer Part") "0402B103K500NT") (field (name "Manufacturer") "FH(风华)"))
      (libsource (lib "") (part "0402B103K500NT"))
    )
    (comp (ref "C140")
      (value "1uF")
      (fields
        (field (name "Manufacturer Part") "CL05A105KO5NNNC")
        (field (name "Manufacturer") "SAMSUNG(三星)")
      )
      (libsource (lib "") (part "CL05A105KO5NNNC"))
    )
    (comp (ref "C141")
      (value "1uF")
      (fields
        (field (name "Manufacturer Part") "CL05A105KO5NNNC")
        (field (name "Manufacturer") "SAMSUNG(三星)")
      )
      (libsource (lib "") (part "CL05A105KO5NNNC"))
    )
    (comp (ref "C142")
      (value "10nF")
      (fields (field (name "Manufacturer Part") "0402B103K500NT") (field (name "Manufacturer") "FH(风华)"))
      (libsource (lib "") (part "0402B103K500NT"))
    )
    (comp (ref "C143")
      (value "1uF")
      (fields
        (field (name "Manufacturer Part") "CL05A105KO5NNNC")
        (field (name "Manufacturer") "SAMSUNG(三星)")
      )
      (libsource (lib "") (part "CL05A105KO5NNNC"))
    )
    (comp (ref "C144")
      (value "10nF")
      (fields (field (name "Manufacturer Part") "0402B103K500NT") (field (name "Manufacturer") "FH(风华)"))
      (libsource (lib "") (part "0402B103K500NT"))
    )
    (comp (ref "C145")
      (value "10uF")
      (fields (field (name "Manufacturer Part") "RVT2A100M0607") (field (name "Manufacturer") "ROQANG(容强)"))
      (libsource (lib "") (part "RVT2A100M0607"))
    )
    (comp (ref "C146")
      (value "22uF")
      (fields (field (name "Manufacturer Part") "RT1J220M0607") (field (name "Manufacturer") "ROQANG(容强)"))
      (libsource (lib "") (part "RT1J220M0607"))
    )
    (comp (ref "R19")
      (value "1Ω")
      (fields
        (field (name "Manufacturer Part") "0105WHF100KTDE")
        (field (name "Manufacturer") "UNI-ROYAL(厚声)")
      )
      (libsource (lib "") (part "0105WHF100KTDE"))
    )
    (comp (ref "R20")
      (value "1Ω")
      (fields
        (field (name "Manufacturer Part") "0105WHF100KTDE")
        (field (name "Manufacturer") "UNI-ROYAL(厚声)")
      )
      (libsource (lib "") (part "0105WHF100KTDE"))
    )
    (comp (ref "R25")
      (value "10kΩ")
      (fields
        (field (name "Manufacturer Part") "0402WGF1002TCE")
        (field (name "Manufacturer") "UNI-ROYAL(厚声)")
      )
      (libsource (lib "") (part "0402WGF1002TCE"))
    )
    (comp (ref "R26")
      (value "4.99Ω")
      (fields (field (name "Manufacturer Part") "RTT014R99FTH") (field (name "Manufacturer") "RALEC(旺诠)"))
      (libsource (lib "") (part "RTT014R99FTH"))
    )
    (comp (ref "R27")
      (value "0Ω")
      (fields
        (field (name "Manufacturer Part") "0402WGF0000TCE")
        (field (name "Manufacturer") "UNI-ROYAL(厚声)")
      )
      (libsource (lib "") (part "0402WGF0000TCE"))
    )
    (comp (ref "R34")
      (value "0Ω")
      (fields
        (field (name "Manufacturer Part") "0402WGF0000TCE")
        (field (name "Manufacturer") "UNI-ROYAL(厚声)")
      )
      (libsource (lib "") (part "0402WGF0000TCE"))
    )
    (comp (ref "R35")
      (value "10kΩ")
      (fields
        (field (name "Manufacturer Part") "0402WGF1002TCE")
        (field (name "Manufacturer") "UNI-ROYAL(厚声)")
      )
      (libsource (lib "") (part "0402WGF1002TCE"))
    )
    (comp (ref "R36")
      (value "4.99Ω")
      (fields (field (name "Manufacturer Part") "RTT014R99FTH") (field (name "Manufacturer") "RALEC(旺诠)"))
      (libsource (lib "") (part "RTT014R99FTH"))
    )
    (comp (ref "U9")
      (value "SGM2036-0.8YN5G/TR")
      (fields (field (name "Manufacturer") "SGMICRO(圣邦微)"))
      (libsource (lib "") (part "SGM2036-0.8YN5G/TR"))
    )
    (comp (ref "U11")
      (value "SGM2036-0.8YN5G/TR")
      (fields (field (name "Manufacturer") "SGMICRO(圣邦微)"))
      (libsource (lib "") (part "SGM2036-0.8YN5G/TR"))
    )
    (comp (ref "U12")
      (value "AMS1117-1.8_C498120")
      (fields (field (name "Manufacturer Part") "AMS1117-1.8") (field (name "Manufacturer") "HGC(华冠)"))
      (libsource (lib "") (part "AMS1117-1.8_C498120"))
    )
  )
  (nets
    (net (code "1") (name "0.8V-1") (class "Default")
      (node (ref "C143") (pin "1") (pinfunction "1_1") (pintype "input"))
      (node (ref "C144") (pin "1") (pinfunction "1_1") (pintype "input"))
      (node (ref "R34") (pin "2") (pinfunction "2_2") (pintype "input"))
      (node (ref "U11") (pin "5") (pinfunction "OUT_5") (pintype "unspecified"))
    )
    (net (code "2") (name "0.8V-2") (class "Default")
      (node (ref "C139") (pin "1") (pinfunction "1_1") (pintype "input"))
      (node (ref "C35") (pin "1") (pinfunction "1_1") (pintype "input"))
      (node (ref "C45") (pin "1") (pinfunction "1_1") (pintype "input"))
      (node (ref "C48") (pin "1") (pinfunction "1_1") (pintype "input"))
      (node (ref "C90") (pin "1") (pinfunction "1_1") (pintype "input"))
      (node (ref "R27") (pin "2") (pinfunction "2_2") (pintype "input"))
      (node (ref "U1") (pin "14") (pinfunction "PLL_VDD_14") (pintype "unspecified"))
      (node (ref "U1") (pin "15") (pinfunction "VDDIO_08_0_15") (pintype "unspecified"))
      (node (ref "U1") (pin "18") (pinfunction "VDDIO_08_1_18") (pintype "unspecified"))
      (node (ref "U10") (pin "14") (pinfunction "PLL_VDD_14") (pintype "unspecified"))
      (node (ref "U10") (pin "15") (pinfunction "VDDIO_08_0_15") (pintype "unspecified"))
      (node (ref "U9") (pin "5") (pinfunction "OUT_5") (pintype "unspecified"))
    )
    (net (code "3") (name "0.8V-3") (class "Default")
      (node (ref "C32") (pin "1") (pinfunction "1_1") (pintype "input"))
      (node (ref "U10") (pin "18") (pinfunction "VDDIO_08_1_18") (pintype "unspecified"))
    )
    (net (code "4") (name "1.8-3") (class "Default")
      (node (ref "C33") (pin "1") (pinfunction "1_1") (pintype "input"))
      (node (ref "U10") (pin "17") (pinfunction "VDDIO_18_1_17") (pintype "unspecified"))
    )
    (net (code "5") (name "1.8-12") (class "Default")
      (node (ref "C34") (pin "1") (pinfunction "1_1") (pintype "input"))
      (node (ref "U10") (pin "16") (pinfunction "VDDIO_18_0_16") (pintype "unspecified"))
    )
    (net (code "6") (name "1.8V-1") (class "Default")
      (node (ref "C146") (pin "1") (pinfunction "1_1") (pintype "input"))
      (node (ref "U12") (pin "2") (pinfunction "VOUT_2") (pintype "unspecified"))
      (node (ref "U12") (pin "4") (pinfunction "TAB_4") (pintype "unspecified"))
    )
    (net (code "7") (name "1.8V-2") (class "Default")
      (node (ref "C46") (pin "1") (pinfunction "1_1") (pintype "input"))
      (node (ref "C47") (pin "1") (pinfunction "1_1") (pintype "input"))
      (node (ref "U1") (pin "16") (pinfunction "VDDIO_18_0_16") (pintype "unspecified"))
      (node (ref "U1") (pin "17") (pinfunction "VDDIO_18_1_17") (pintype "unspecified"))
    )
    (net (code "8") (name "3V3") (class "Default")
      (node (ref "C2") (pin "2") (pinfunction "2_2") (pintype "unspecified"))
      (node (ref "C25") (pin "1") (pinfunction "1_1") (pintype "input"))
      (node (ref "C26") (pin "2") (pinfunction "2_2") (pintype "input"))
      (node (ref "C4") (pin "1") (pinfunction "1_1") (pintype "input"))
      (node (ref "C8") (pin "2") (pinfunction "2_2") (pintype "unspecified"))
      (node (ref "C9") (pin "1") (pinfunction "1_1") (pintype "input"))
      (node (ref "DP1") (pin "4") (pinfunction "VCC_4") (pintype "passive"))
      (node (ref "R14") (pin "1") (pinfunction "1_1") (pintype "input"))
      (node (ref "R18") (pin "1") (pinfunction "1_1") (pintype "input"))
      (node (ref "R3") (pin "2") (pinfunction "2_2") (pintype "input"))
      (node (ref "U13") (pin "1") (pinfunction "VDD_1") (pintype "unspecified"))
      (node (ref "U14") (pin "7") (pinfunction "7_7") (pintype "unspecified"))
      (node (ref "U4") (pin "2") (pinfunction "3V3_2") (pintype "unspecified"))
      (node (ref "U5") (pin "5") (pinfunction "VOUT_5") (pintype "unspecified"))
      (node (ref "U7") (pin "8") (pinfunction "VCC_8") (pintype "unspecified"))
      (node (ref "U8") (pin "11") (pinfunction "GND_11") (pintype "unspecified"))
      (node (ref "X2") (pin "10") (pinfunction "10_10") (pintype "unspecified"))
    )
    (net (code "9") (name "5V") (class "Default")
      (node (ref "C5") (pin "1") (pinfunction "1_1") (pintype "input"))
      (node (ref "U2") (pin "2") (pinfunction "5V_2") (pintype "unspecified"))
      (node (ref "U5") (pin "1") (pinfunction "VIN_1") (pintype "unspecified"))
      (node (ref "U5") (pin "3") (pinfunction "EN_3") (pintype "unspecified"))
    )
    (net (code "10") (name "ALERT") (class "Default")
      (node (ref "R4") (pin "1") (pinfunction "1_1") (pintype "unspecified"))
      (node (ref "R5") (pin "2") (pinfunction "2_2") (pintype "input"))
    )
    (net (code "11") (name "BI") (class "Default")
      (node (ref "U14") (pin "1") (pinfunction "1_1") (pintype "unspecified"))
      (node (ref "U3") (pin "10") (pinfunction "B4_10") (pintype "unspecified"))
      (node (ref "U4") (pin "18") (pinfunction "IO10_18") (pintype "unspecified"))
    )
    (net (code "12") (name "BI-IN") (class "Default")
      (node (ref "U10") (pin "25") (pinfunction "CLKO_25") (pintype "unspecified"))
    )
    (net (code "13") (name "BM_BI") (class "Default")
      (node (ref "U3") (pin "5") (pinfunction "A4_5") (pintype "unspecified"))
    )
    (net (code "14") (name "BO1") (class "Default")
      (node (ref "U1") (pin "25") (pinfunction "CLKO_25") (pintype "unspecified"))
      (node (ref "U10") (pin "12") (pinfunction "CLKI_12") (pintype "unspecified"))
    )
    (net (code "15") (name "BO2") (class "Default")
      (node (ref "U1") (pin "12") (pinfunction "CLKI_12") (pintype "unspecified"))
    )
    (net (code "16") (name "CI") (class "Default")
      (node (ref "U3") (pin "3") (pinfunction "A2_3") (pintype "unspecified"))
    )
    (net (code "17") (name "CI-IN") (class "Default")
      (node (ref "U10") (pin "28") (pinfunction "NRSTO_28") (pintype "unspecified"))
    )
    (net (code "18") (name "CLK-IN") (class "Default")
      (node (ref "U10") (pin "29") (pinfunction "BO_29") (pintype "unspecified"))
    )
    (net (code "19") (name "CLK1") (class "Default")
      (node (ref "U1") (pin "29") (pinfunction "BO_29") (pintype "unspecified"))
      (node (ref "U10") (pin "8") (pinfunction "BI_8") (pintype "unspecified"))
    )
    (net (code "20") (name "CLK2") (class "Default")
      (node (ref "U1") (pin "8") (pinfunction "BI_8") (pintype "unspecified"))
    )
    (net (code "21") (name "CLKI") (class "Default")
      (node (ref "U4") (pin "13") (pinfunction "IO19_13") (pintype "unspecified"))
    )
    (net (code "22") (name "CO1") (class "Default")
      (node (ref "U1") (pin "28") (pinfunction "NRSTO_28") (pintype "unspecified"))
      (node (ref "U10") (pin "9") (pinfunction "NRSTI_9") (pintype "unspecified"))
    )
    (net (code "23") (name "CO2") (class "Default")
      (node (ref "U1") (pin "9") (pinfunction "NRSTI_9") (pintype "unspecified"))
    )
    (net (code "24") (name "FAN_ALERT") (class "Default")
      (node (ref "U4") (pin "20") (pinfunction "IO12_20") (pintype "unspecified"))
    )
    (net (code "25") (name "FAN_PWM") (class "Default")
      (node (ref "R3") (pin "1") (pinfunction "1_1") (pintype "input"))
      (node (ref "U13") (pin "4") (pinfunction "FAN_4") (pintype "unspecified"))
      (node (ref "U2") (pin "4") (pinfunction "FAN_PWM_4") (pintype "unspecified"))
    )
    (net (code "26") (name "FAN_TACH") (class "Default")
      (node (ref "R4") (pin "2") (pinfunction "2_2") (pintype "unspecified"))
      (node (ref "U13") (pin "6") (pinfunction "ALERT#/TACH_6") (pintype "unspecified"))
      (node (ref "U2") (pin "3") (pinfunction "FAN_TACH_3") (pintype "unspecified"))
    )
    (net (code "27") (name "GND") (class "Default")
      (node (ref "C14") (pin "1") (pinfunction "1_1") (pintype "input"))
      (node (ref "C145") (pin "2") (pinfunction "2_2") (pintype "input"))
      (node (ref "C2") (pin "1") (pinfunction "1_1") (pintype "unspecified"))
      (node (ref "C23") (pin "2") (pinfunction "2_2") (pintype "input"))
      (node (ref "C24") (pin "2") (pinfunction "2_2") (pintype "input"))
      (node (ref "C26") (pin "1") (pinfunction "1_1") (pintype "input"))
      (node (ref "C3") (pin "2") (pinfunction "2_2") (pintype "unspecified"))
      (node (ref "C4") (pin "2") (pinfunction "2_2") (pintype "input"))
      (node (ref "C5") (pin "2") (pinfunction "2_2") (pintype "input"))
      (node (ref "C6") (pin "1") (pinfunction "1_1") (pintype "unspecified"))
      (node (ref "C7") (pin "1") (pinfunction "1_1") (pintype "unspecified"))
      (node (ref "C8") (pin "1") (pinfunction "1_1") (pintype "unspecified"))
      (node (ref "C9") (pin "2") (pinfunction "2_2") (pintype "input"))
      (node (ref "DP1") (pin "1") (pinfunction "GND_1") (pintype "passive"))
      (node (ref "LED1") (pin "4") (pinfunction "-_4") (pintype "unspecified"))
      (node (ref "LED1") (pin "5") (pinfunction "-_5") (pintype "unspecified"))
      (node (ref "LED1") (pin "6") (pinfunction "-_6") (pintype "unspecified"))
      (node (ref "LED2") (pin "4") (pinfunction "-_4") (pintype "unspecified"))
      (node (ref "LED2") (pin "5") (pinfunction "-_5") (pintype "unspecified"))
      (node (ref "LED2") (pin "6") (pinfunction "-_6") (pintype "unspecified"))
      (node (ref "Q2") (pin "3") (pinfunction "S_3") (pintype "unspecified"))
      (node (ref "R26") (pin "1") (pinfunction "1_1") (pintype "unspecified"))
      (node (ref "R36") (pin "1") (pinfunction "1_1") (pintype "unspecified"))
      (node (ref "R5") (pin "1") (pinfunction "1_1") (pintype "input"))
      (node (ref "R7") (pin "2") (pinfunction "2_2") (pintype "unspecified"))
      (node (ref "U12") (pin "3") (pinfunction "VIN_3") (pintype "unspecified"))
      (node (ref "U13") (pin "5") (pinfunction "GND_5") (pintype "unspecified"))
      (node (ref "U14") (pin "8") (pinfunction "8_8") (pintype "unspecified"))
      (node (ref "U2") (pin "1") (pinfunction "GND_1") (pintype "unspecified"))
      (node (ref "U4") (pin "1") (pinfunction "GND_1") (pintype "unspecified"))
      (node (ref "U5") (pin "2") (pinfunction "GND_2") (pintype "unspecified"))
      (node (ref "U6") (pin "11") (pinfunction "EP_11") (pintype "passive"))
      (node (ref "U8") (pin "4") (pinfunction "A1_4") (pintype "unspecified"))
      (node (ref "U8") (pin "5") (pinfunction "A0_5") (pintype "unspecified"))
      (node (ref "U8") (pin "6") (pinfunction "GND_6") (pintype "unspecified"))
      (node (ref "X2") (pin "6") (pinfunction "6_6") (pintype "unspecified"))
      (node (ref "X2") (pin "7") (pinfunction "7_7") (pintype "unspecified"))
      (node (ref "X2") (pin "8") (pinfunction "8_8") (pintype "unspecified"))
      (node (ref "X2") (pin "9") (pinfunction "9_9") (pintype "unspecified"))
    )
    (net (code "28") (name "GND1") (class "Default")
      (node (ref "C10") (pin "2") (pinfunction "2_2") (pintype "input"))
      (node (ref "C110") (pin "2") (pinfunction "2_2") (pintype "unspecified"))
      (node (ref "C111") (pin "2") (pinfunction "2_2") (pintype "unspecified"))
      (node (ref "C112") (pin "2") (pinfunction "2_2") (pintype "unspecified"))
      (node (ref "C113") (pin "2") (pinfunction "2_2") (pintype "input"))
      (node (ref "C114") (pin "2") (pinfunction "2_2") (pintype "input"))
      (node (ref "C139") (pin "2") (pinfunction "2_2") (pintype "input"))
      (node (ref "C140") (pin "2") (pinfunction "2_2") (pintype "input"))
      (node (ref "C141") (pin "2") (pinfunction "2_2") (pintype "input"))
      (node (ref "C142") (pin "2") (pinfunction "2_2") (pintype "input"))
      (node (ref "C143") (pin "2") (pinfunction "2_2") (pintype "input"))
      (node (ref "C144") (pin "2") (pinfunction "2_2") (pintype "input"))
      (node (ref "C146") (pin "2") (pinfunction "2_2") (pintype "input"))
      (node (ref "C31") (pin "1") (pinfunction "1_1") (pintype "input"))
      (node (ref "C32") (pin "2") (pinfunction "2_2") (pintype "input"))
      (node (ref "C33") (pin "2") (pinfunction "2_2") (pintype "input"))
      (node (ref "C34") (pin "2") (pinfunction "2_2") (pintype "input"))
      (node (ref "C35") (pin "2") (pinfunction "2_2") (pintype "input"))
      (node (ref "C37") (pin "2") (pinfunction "2_2") (pintype "input"))
      (node (ref "C44") (pin "1") (pinfunction "1_1") (pintype "input"))
      (node (ref "C45") (pin "2") (pinfunction "2_2") (pintype "input"))
      (node (ref "C46") (pin "2") (pinfunction "2_2") (pintype "input"))
      (node (ref "C47") (pin "2") (pinfunction "2_2") (pintype "input"))
      (node (ref "C48") (pin "2") (pinfunction "2_2") (pintype "input"))
      (node (ref "C73") (pin "2") (pinfunction "2_2") (pintype "unspecified"))
      (node (ref "C74") (pin "2") (pinfunction "2_2") (pintype "unspecified"))
      (node (ref "C75") (pin "2") (pinfunction "2_2") (pintype "unspecified"))
      (node (ref "C76") (pin "2") (pinfunction "2_2") (pintype "input"))
      (node (ref "C77") (pin "2") (pinfunction "2_2") (pintype "input"))
      (node (ref "C79") (pin "2") (pinfunction "2_2") (pintype "input"))
      (node (ref "C80") (pin "2") (pinfunction "2_2") (pintype "unspecified"))
      (node (ref "C81") (pin "2") (pinfunction "2_2") (pintype "unspecified"))
      (node (ref "C82") (pin "2") (pinfunction "2_2") (pintype "unspecified"))
      (node (ref "C83") (pin "2") (pinfunction "2_2") (pintype "input"))
      (node (ref "C89") (pin "2") (pinfunction "2_2") (pintype "input"))
      (node (ref "C90") (pin "2") (pinfunction "2_2") (pintype "input"))
      (node (ref "R15") (pin "1") (pinfunction "1_1") (pintype "input"))
      (node (ref "R16") (pin "1") (pinfunction "1_1") (pintype "input"))
      (node (ref "R17") (pin "1") (pinfunction "1_1") (pintype "input"))
      (node (ref "R19") (pin "2") (pinfunction "2_2") (pintype "unspecified"))
      (node (ref "R20") (pin "2") (pinfunction "2_2") (pintype "unspecified"))
      (node (ref "R21") (pin "1") (pinfunction "1_1") (pintype "input"))
      (node (ref "R22") (pin "1") (pinfunction "1_1") (pintype "input"))
      (node (ref "R6") (pin "1") (pinfunction "1_1") (pintype "input"))
      (node (ref "U1") (pin "13") (pinfunction "PLL_VSS_13") (pintype "unspecified"))
      (node (ref "U1") (pin "19") (pinfunction "VSS_19") (pintype "unspecified"))
      (node (ref "U1") (pin "20") (pinfunction "PIN_MODE_20") (pintype "unspecified"))
      (node (ref "U1") (pin "34") (pinfunction "VSS_34") (pintype "unspecified"))
      (node (ref "U10") (pin "13") (pinfunction "PLL_VSS_13") (pintype "unspecified"))
      (node (ref "U10") (pin "19") (pinfunction "VSS_19") (pintype "unspecified"))
      (node (ref "U10") (pin "20") (pinfunction "PIN_MODE_20") (pintype "unspecified"))
      (node (ref "U10") (pin "34") (pinfunction "VSS_34") (pintype "unspecified"))
      (node (ref "U11") (pin "2") (pinfunction "GND_2") (pintype "unspecified"))
      (node (ref "U9") (pin "2") (pinfunction "GND_2") (pintype "unspecified"))
    )
    (net (code "29") (name "LEDX_B") (class "Default")
      (node (ref "LED2") (pin "3") (pinfunction "+_3") (pintype "unspecified"))
      (node (ref "U4") (pin "30") (pinfunction "IO37_30") (pintype "unspecified"))
    )
    (net (code "30") (name "LEDX_G") (class "Default")
      (node (ref "LED2") (pin "1") (pinfunction "+_1") (pintype "unspecified"))
      (node (ref "U4") (pin "29") (pinfunction "IO36_29") (pintype "unspecified"))
    )
    (net (code "31") (name "LEDX_R") (class "Default")
      (node (ref "LED2") (pin "2") (pinfunction "+_2") (pintype "unspecified"))
      (node (ref "U4") (pin "28") (pinfunction "IO35_28") (pintype "unspecified"))
    )
    (net (code "32") (name "LEDZ_B") (class "Default")
      (node (ref "LED1") (pin "3") (pinfunction "+_3") (pintype "unspecified"))
      (node (ref "U4") (pin "7") (pinfunction "IO7_7") (pintype "unspecified"))
    )
    (net (code "33") (name "LEDZ_G") (class "Default")
      (node (ref "LED1") (pin "1") (pinfunction "+_1") (pintype "unspecified"))
      (node (ref "U4") (pin "6") (pinfunction "IO6_6") (pintype "unspecified"))
    )
    (net (code "34") (name "LEDZ_R") (class "Default")
      (node (ref "LED1") (pin "2") (pinfunction "+_2") (pintype "unspecified"))
      (node (ref "U4") (pin "5") (pinfunction "IO5_5") (pintype "unspecified"))
    )
    (net (code "35") (name "MTCK") (class "Default")
      (node (ref "U4") (pin "32") (pinfunction "IO39_32") (pintype "unspecified"))
      (node (ref "X2") (pin "2") (pinfunction "2_2") (pintype "unspecified"))
    )
    (net (code "36") (name "MTDI") (class "Default")
      (node (ref "U4") (pin "34") (pinfunction "IO41_34") (pintype "unspecified"))
      (node (ref "X2") (pin "4") (pinfunction "4_4") (pintype "unspecified"))
    )
    (net (code "37") (name "MTDO") (class "Default")
      (node (ref "U4") (pin "33") (pinfunction "IO40_33") (pintype "unspecified"))
      (node (ref "X2") (pin "3") (pinfunction "3_3") (pintype "unspecified"))
    )
    (net (code "38") (name "MTMS") (class "Default")
      (node (ref "U4") (pin "35") (pinfunction "IO42_35") (pintype "unspecified"))
      (node (ref "X2") (pin "1") (pinfunction "1_1") (pintype "unspecified"))
    )
    (net (code "39") (name "NRSTI-IN") (class "Default")
      (node (ref "U10") (pin "26") (pinfunction "CO_26") (pintype "unspecified"))
    )
    (net (code "40") (name "Net-(C16-Pad1)") (class "Default")
      (node (ref "C16") (pin "1") (pinfunction "1_1") (pintype "input"))
      (node (ref "R9") (pin "1") (pinfunction "1_1") (pintype "input"))
    )
    (net (code "41") (name "Net-(C17-Pad2)") (class "Default")
      (node (ref "C17") (pin "2") (pinfunction "2_2") (pintype "unspecified"))
      (node (ref "R10") (pin "2") (pinfunction "2_2") (pintype "unspecified"))
    )
    (net (code "42") (name "Net-(Q1-G)") (class "Default")
      (node (ref "Q1") (pin "4") (pinfunction "G_4") (pintype "unspecified"))
      (node (ref "U6") (pin "7") (pinfunction "HDRV_7") (pintype "output"))
    )
    (net (code "43") (name "Net-(Q2-G)") (class "Default")
      (node (ref "Q2") (pin "4") (pinfunction "G_4") (pintype "unspecified"))
      (node (ref "R7") (pin "1") (pinfunction "1_1") (pintype "unspecified"))
      (node (ref "U6") (pin "9") (pinfunction "LDRVOC_9") (pintype "output"))
    )
    (net (code "44") (name "Net-(R11-Pad1)") (class "Default")
      (node (ref "R11") (pin "1") (pinfunction "1_1") (pintype "input"))
      (node (ref "R12") (pin "1") (pinfunction "1_1") (pintype "input"))
    )
    (net (code "45") (name "Net-(U1-ADDR0)") (class "Default")
      (node (ref "R6") (pin "2") (pinfunction "2_2") (pintype "input"))
      (node (ref "U1") (pin "4") (pinfunction "ADDR0_4") (pintype "unspecified"))
    )
    (net (code "46") (name "Net-(U1-ADDR1)") (class "Default")
      (node (ref "R21") (pin "2") (pinfunction "2_2") (pintype "input"))
      (node (ref "U1") (pin "5") (pinfunction "ADDR1_5") (pintype "unspecified"))
    )
    (net (code "47") (name "Net-(U1-ADDR2)") (class "Default")
      (node (ref "R22") (pin "2") (pinfunction "2_2") (pintype "input"))
      (node (ref "U1") (pin "6") (pinfunction "ADDR2_6") (pintype "unspecified"))
    )
    (net (code "48") (name "Net-(U1-VDD1_0)") (class "Default")
      (node (ref "C43") (pin "1") (pinfunction "1_1") (pintype "input"))
      (node (ref "C44") (pin "2") (pinfunction "2_2") (pintype "input"))
      (node (ref "U1") (pin "3") (pinfunction "VDD1_0_3") (pintype "unspecified"))
    )
    (net (code "49") (name "Net-(U1-VDD1_1)") (class "Default")
      (node (ref "C37") (pin "1") (pinfunction "1_1") (pintype "input"))
      (node (ref "C38") (pin "2") (pinfunction "2_2") (pintype "input"))
      (node (ref "U1") (pin "30") (pinfunction "VDD1_1_30") (pintype "unspecified"))
    )
    (net (code "50") (name "Net-(U1-VDD2_0)") (class "Default")
      (node (ref "C42") (pin "1") (pinfunction "1_1") (pintype "input"))
      (node (ref "C43") (pin "2") (pinfunction "2_2") (pintype "input"))
      (node (ref "U1") (pin "2") (pinfunction "VDD2_0_2") (pintype "unspecified"))
    )
    (net (code "51") (name "Net-(U1-VDD2_1)") (class "Default")
      (node (ref "C38") (pin "1") (pinfunction "1_1") (pintype "input"))
      (node (ref "C39") (pin "2") (pinfunction "2_2") (pintype "input"))
      (node (ref "U1") (pin "31") (pinfunction "VDD2_1_31") (pintype "unspecified"))
    )
    (net (code "52") (name "Net-(U1-VDD3_0)") (class "Default")
      (node (ref "C41") (pin "1") (pinfunction "1_1") (pintype "input"))
      (node (ref "C42") (pin "2") (pinfunction "2_2") (pintype "input"))
      (node (ref "U1") (pin "1") (pinfunction "VDD3_0_1") (pintype "unspecified"))
    )
    (net (code "53") (name "Net-(U1-VDD3_1)") (class "Default")
      (node (ref "C39") (pin "1") (pinfunction "1_1") (pintype "input"))
      (node (ref "C40") (pin "2") (pinfunction "2_2") (pintype "input"))
      (node (ref "U1") (pin "32") (pinfunction "VDD3_1_32") (pintype "unspecified"))
    )
    (net (code "54") (name "Net-(U3-GND)") (class "Default")
      (node (ref "C1") (pin "1") (pinfunction "1_1") (pintype "unspecified"))
      (node (ref "U3") (pin "1") (pinfunction "VCCA_1") (pintype "unspecified"))
      (node (ref "U3") (pin "7") (pinfunction "GND_7") (pintype "unspecified"))
      (node (ref "U3") (pin "8") (pinfunction "OE_8") (pintype "unspecified"))
    )
    (net (code "55") (name "Net-(U3-VCCB)") (class "Default")
      (node (ref "C1") (pin "2") (pinfunction "2_2") (pintype "unspecified"))
      (node (ref "U3") (pin "14") (pinfunction "VCCB_14") (pintype "unspecified"))
    )
    (net (code "56") (name "Net-(U4-EN)") (class "Default")
      (node (ref "C3") (pin "1") (pinfunction "1_1") (pintype "unspecified"))
      (node (ref "R18") (pin "2") (pinfunction "2_2") (pintype "input"))
      (node (ref "U4") (pin "3") (pinfunction "EN_3") (pintype "unspecified"))
    )
    (net (code "57") (name "Net-(U6-BOOT)") (class "Default")
      (node (ref "C13") (pin "1") (pinfunction "1_1") (pintype "unspecified"))
      (node (ref "U6") (pin "6") (pinfunction "BOOT_6") (pintype "passive"))
    )
    (net (code "58") (name "Net-(U6-BP)") (class "Default")
      (node (ref "C14") (pin "2") (pinfunction "2_2") (pintype "input"))
      (node (ref "R8") (pin "2") (pinfunction "2_2") (pintype "input"))
      (node (ref "U6") (pin "10") (pinfunction "BP_10") (pintype "passive"))
    )
    (net (code "59") (name "Net-(U6-COMP)") (class "Default")
      (node (ref "C15") (pin "2") (pinfunction "2_2") (pintype "unspecified"))
      (node (ref "C16") (pin "2") (pinfunction "2_2") (pintype "input"))
      (node (ref "C18") (pin "1") (pinfunction "1_1") (pintype "unspecified"))
      (node (ref "C19") (pin "1") (pinfunction "1_1") (pintype "unspecified"))
      (node (ref "C20") (pin "1") (pinfunction "1_1") (pintype "unspecified"))
      (node (ref "C21") (pin "2") (pinfunction "2_2") (pintype "unspecified"))
      (node (ref "C22") (pin "2") (pinfunction "2_2") (pintype "input"))
      (node (ref "R11") (pin "2") (pinfunction "2_2") (pintype "input"))
      (node (ref "U6") (pin "4") (pinfunction "COMP_4") (pintype "output"))
    )
    (net (code "60") (name "Net-(U6-PGOOD)") (class "Default")
      (node (ref "R8") (pin "1") (pinfunction "1_1") (pintype "input"))
      (node (ref "U6") (pin "3") (pinfunction "PGOOD_3") (pintype "unspecified"))
    )
    (net (code "61") (name "Net-(U6-SW)") (class "Default")
      (node (ref "C13") (pin "2") (pinfunction "2_2") (pintype "unspecified"))
      (node (ref "L1") (pin "1") (pinfunction "1_1") (pintype "unspecified"))
      (node (ref "Q1") (pin "3") (pinfunction "S_3") (pintype "unspecified"))
      (node (ref "Q2") (pin "5") (pinfunction "D_5") (pintype "unspecified"))
      (node (ref "U6") (pin "8") (pinfunction "SW_8") (pintype "passive"))
    )
    (net (code "62") (name "Net-(U6-VDD)") (class "Default")
      (node (ref "C18") (pin "2") (pinfunction "2_2") (pintype "unspecified"))
      (node (ref "C19") (pin "2") (pinfunction "2_2") (pintype "unspecified"))
      (node (ref "C20") (pin "2") (pinfunction "2_2") (pintype "unspecified"))
      (node (ref "C21") (pin "1") (pinfunction "1_1") (pintype "unspecified"))
      (node (ref "C22") (pin "1") (pinfunction "1_1") (pintype "input"))
      (node (ref "Q1") (pin "5") (pinfunction "D_5") (pintype "unspecified"))
      (node (ref "U6") (pin "1") (pinfunction "VDD_1") (pintype "passive"))
    )
    (net (code "63") (name "Net-(U7-FS0)") (class "Default")
      (node (ref "R13") (pin "1") (pinfunction "1_1") (pintype "unspecified"))
      (node (ref "U7") (pin "5") (pinfunction "FS0_5") (pintype "unspecified"))
    )
    (net (code "64") (name "Net-(U7-GND)") (class "Default")
      (node (ref "C25") (pin "2") (pinfunction "2_2") (pintype "input"))
      (node (ref "R13") (pin "2") (pinfunction "2_2") (pintype "unspecified"))
      (node (ref "U7") (pin "4") (pinfunction "GND_4") (pintype "unspecified"))
    )
    (net (code "65") (name "Net-(U9-BP{slash}FB)") (class "Default")
      (node (ref "C89") (pin "1") (pinfunction "1_1") (pintype "input"))
      (node (ref "R27") (pin "1") (pinfunction "1_1") (pintype "input"))
      (node (ref "U9") (pin "4") (pinfunction "BP/FB_4") (pintype "unspecified"))
    )
    (net (code "66") (name "Net-(U9-EN)") (class "Default")
      (node (ref "R25") (pin "2") (pinfunction "2_2") (pintype "input"))
      (node (ref "U9") (pin "3") (pinfunction "EN_3") (pintype "unspecified"))
    )
    (net (code "67") (name "Net-(U9-IN)") (class "Default")
      (node (ref "C140") (pin "1") (pinfunction "1_1") (pintype "input"))
      (node (ref "R25") (pin "1") (pinfunction "1_1") (pintype "input"))
      (node (ref "R26") (pin "2") (pinfunction "2_2") (pintype "unspecified"))
      (node (ref "U9") (pin "1") (pinfunction "IN_1") (pintype "unspecified"))
    )
    (net (code "68") (name "Net-(U10-ADDR0)") (class "Default")
      (node (ref "R17") (pin "2") (pinfunction "2_2") (pintype "input"))
      (node (ref "U10") (pin "4") (pinfunction "ADDR0_4") (pintype "unspecified"))
    )
    (net (code "69") (name "Net-(U10-ADDR1)") (class "Default")
      (node (ref "R16") (pin "2") (pinfunction "2_2") (pintype "input"))
      (node (ref "U10") (pin "5") (pinfunction "ADDR1_5") (pintype "unspecified"))
    )
    (net (code "70") (name "Net-(U10-ADDR2)") (class "Default")
      (node (ref "R15") (pin "2") (pinfunction "2_2") (pintype "input"))
      (node (ref "U10") (pin "6") (pinfunction "ADDR2_6") (pintype "unspecified"))
    )
    (net (code "71") (name "Net-(U10-VDD1_0)") (class "Default")
      (node (ref "C30") (pin "1") (pinfunction "1_1") (pintype "input"))
      (node (ref "C31") (pin "2") (pinfunction "2_2") (pintype "input"))
      (node (ref "U10") (pin "3") (pinfunction "VDD1_0_3") (pintype "unspecified"))
    )
    (net (code "72") (name "Net-(U10-VDD1_1)") (class "Default")
      (node (ref "C10") (pin "1") (pinfunction "1_1") (pintype "input"))
      (node (ref "C11") (pin "2") (pinfunction "2_2") (pintype "input"))
      (node (ref "U10") (pin "30") (pinfunction "VDD1_1_30") (pintype "unspecified"))
    )
    (net (code "73") (name "Net-(U10-VDD2_0)") (class "Default")
      (node (ref "C29") (pin "1") (pinfunction "1_1") (pintype "input"))
      (node (ref "C30") (pin "2") (pinfunction "2_2") (pintype "input"))
      (node (ref "U10") (pin "2") (pinfunction "VDD2_0_2") (pintype "unspecified"))
    )
    (net (code "74") (name "Net-(U10-VDD2_1)") (class "Default")
      (node (ref "C11") (pin "1") (pinfunction "1_1") (pintype "input"))
      (node (ref "C12") (pin "2") (pinfunction "2_2") (pintype "input"))
      (node (ref "U10") (pin "31") (pinfunction "VDD2_1_31") (pintype "unspecified"))
    )
    (net (code "75") (name "Net-(U10-VDD3_0)") (class "Default")
      (node (ref "C28") (pin "1") (pinfunction "1_1") (pintype "input"))
      (node (ref "C29") (pin "2") (pinfunction "2_2") (pintype "input"))
      (node (ref "U10") (pin "1") (pinfunction "VDD3_0_1") (pintype "unspecified"))
    )
    (net (code "76") (name "Net-(U10-VDD3_1)") (class "Default")
      (node (ref "C12") (pin "1") (pinfunction "1_1") (pintype "input"))
      (node (ref "C27") (pin "2") (pinfunction "2_2") (pintype "input"))
      (node (ref "U10") (pin "32") (pinfunction "VDD3_1_32") (pintype "unspecified"))
    )
    (net (code "77") (name "Net-(U11-BP{slash}FB)") (class "Default")
      (node (ref "C142") (pin "1") (pinfunction "1_1") (pintype "input"))
      (node (ref "R34") (pin "1") (pinfunction "1_1") (pintype "input"))
      (node (ref "U11") (pin "4") (pinfunction "BP/FB_4") (pintype "unspecified"))
    )
    (net (code "78") (name "Net-(U11-EN)") (class "Default")
      (node (ref "R35") (pin "2") (pinfunction "2_2") (pintype "input"))
      (node (ref "U11") (pin "3") (pinfunction "EN_3") (pintype "unspecified"))
    )
    (net (code "79") (name "Net-(U11-IN)") (class "Default")
      (node (ref "C141") (pin "1") (pinfunction "1_1") (pintype "input"))
      (node (ref "R35") (pin "1") (pinfunction "1_1") (pintype "input"))
      (node (ref "R36") (pin "2") (pinfunction "2_2") (pintype "unspecified"))
      (node (ref "U11") (pin "1") (pinfunction "IN_1") (pintype "unspecified"))
    )
    (net (code "80") (name "Net-(U12-GND)") (class "Default")
      (node (ref "C145") (pin "1") (pinfunction "1_1") (pintype "input"))
      (node (ref "U12") (pin "1") (pinfunction "GND_1") (pintype "unspecified"))
    )
    (net (code "81") (name "Net-(U13-DN)") (class "Default")
      (node (ref "C36") (pin "2") (pinfunction "2_2") (pintype "input"))
      (node (ref "R2") (pin "2") (pinfunction "2_2") (pintype "unspecified"))
      (node (ref "U13") (pin "3") (pinfunction "DN_3") (pintype "unspecified"))
    )
    (net (code "82") (name "Net-(U13-DP)") (class "Default")
      (node (ref "C36") (pin "1") (pinfunction "1_1") (pintype "input"))
      (node (ref "R1") (pin "2") (pinfunction "2_2") (pintype "unspecified"))
      (node (ref "U13") (pin "2") (pinfunction "DP_2") (pintype "unspecified"))
    )
    (net (code "83") (name "OUT0") (class "Default")
      (node (ref "C15") (pin "1") (pinfunction "1_1") (pintype "unspecified"))
      (node (ref "C17") (pin "1") (pinfunction "1_1") (pintype "unspecified"))
      (node (ref "R9") (pin "2") (pinfunction "2_2") (pintype "input"))
      (node (ref "U6") (pin "5") (pinfunction "FB_5") (pintype "unspecified"))
      (node (ref "U7") (pin "6") (pinfunction "OUT0_6") (pintype "unspecified"))
    )
    (net (code "84") (name "OUT1") (class "Default")
      (node (ref "U7") (pin "7") (pinfunction "OUT1_7") (pintype "unspecified"))
    )
    (net (code "85") (name "PGOOD") (class "Default")
      (node (ref "R14") (pin "2") (pinfunction "2_2") (pintype "input"))
    )
    (net (code "86") (name "P_RX") (class "Default")
      (node (ref "U4") (pin "36") (pinfunction "RXD0_36") (pintype "unspecified"))
    )
    (net (code "87") (name "P_TX") (class "Default")
      (node (ref "U4") (pin "37") (pinfunction "TXD0_37") (pintype "unspecified"))
    )
    (net (code "88") (name "RI1") (class "Default")
      (node (ref "U1") (pin "27") (pinfunction "RI_27") (pintype "unspecified"))
      (node (ref "U10") (pin "10") (pinfunction "RO_10") (pintype "unspecified"))
    )
    (net (code "89") (name "RI2") (class "Default")
      (node (ref "U1") (pin "10") (pinfunction "RO_10") (pintype "unspecified"))
    )
    (net (code "90") (name "RO") (class "Default")
      (node (ref "U3") (pin "2") (pinfunction "A1_2") (pintype "unspecified"))
    )
    (net (code "91") (name "RO-IN") (class "Default")
      (node (ref "U10") (pin "27") (pinfunction "RI_27") (pintype "unspecified"))
    )
    (net (code "92") (name "RST") (class "Default")
      (node (ref "U14") (pin "2") (pinfunction "2_2") (pintype "unspecified"))
      (node (ref "U3") (pin "11") (pinfunction "B3_11") (pintype "unspecified"))
      (node (ref "U4") (pin "39") (pinfunction "IO1_39") (pintype "unspecified"))
    )
    (net (code "93") (name "RST1") (class "Default")
      (node (ref "U1") (pin "26") (pinfunction "CO_26") (pintype "unspecified"))
      (node (ref "U10") (pin "11") (pinfunction "CI_11") (pintype "unspecified"))
    )
    (net (code "94") (name "RST2") (class "Default")
      (node (ref "U1") (pin "11") (pinfunction "CI_11") (pintype "unspecified"))
    )
    (net (code "95") (name "RST_N") (class "Default")
      (node (ref "U3") (pin "4") (pinfunction "A3_4") (pintype "unspecified"))
    )
    (net (code "96") (name "RX") (class "Default")
      (node (ref "U14") (pin "3") (pinfunction "3_3") (pintype "unspecified"))
      (node (ref "U3") (pin "13") (pinfunction "B1_13") (pintype "unspecified"))
      (node (ref "U4") (pin "11") (pinfunction "IO18_11") (pintype "unspecified"))
    )
    (net (code "97") (name "SCL") (class "Default")
      (node (ref "DP1") (pin "2") (pinfunction "SCL_2") (pintype "input"))
      (node (ref "U13") (pin "8") (pinfunction "SMCLK_8") (pintype "unspecified"))
      (node (ref "U14") (pin "6") (pinfunction "6_6") (pintype "unspecified"))
      (node (ref "U4") (pin "25") (pinfunction "IO48_25") (pintype "unspecified"))
      (node (ref "U7") (pin "2") (pinfunction "SCL_2") (pintype "unspecified"))
    )
    (net (code "98") (name "SDA") (class "Default")
      (node (ref "DP1") (pin "3") (pinfunction "SDA_3") (pintype "input"))
      (node (ref "U13") (pin "7") (pinfunction "SMDATA_7") (pintype "unspecified"))
      (node (ref "U14") (pin "5") (pinfunction "5_5") (pintype "unspecified"))
      (node (ref "U4") (pin "24") (pinfunction "IO47_24") (pintype "unspecified"))
      (node (ref "U7") (pin "1") (pinfunction "SDA_1") (pintype "unspecified"))
    )
    (net (code "99") (name "TEMP_N") (class "Default")
      (node (ref "R2") (pin "1") (pinfunction "1_1") (pintype "unspecified"))
      (node (ref "U10") (pin "21") (pinfunction "TEMP_N_21") (pintype "unspecified"))
    )
    (net (code "100") (name "TEMP_P") (class "Default")
      (node (ref "R1") (pin "1") (pinfunction "1_1") (pintype "unspecified"))
      (node (ref "U10") (pin "22") (pinfunction "TEMP_P_22") (pintype "unspecified"))
    )
    (net (code "101") (name "TX") (class "Default")
      (node (ref "U14") (pin "4") (pinfunction "4_4") (pintype "unspecified"))
      (node (ref "U3") (pin "12") (pinfunction "B2_12") (pintype "unspecified"))
      (node (ref "U4") (pin "10") (pinfunction "IO17_10") (pintype "unspecified"))
    )
    (net (code "102") (name "VDD") (class "Default")
      (node (ref "U4") (pin "38") (pinfunction "IO2_38") (pintype "unspecified"))
    )
    (net (code "103") (name "VDD1") (class "Default")
      (node (ref "C110") (pin "1") (pinfunction "1_1") (pintype "unspecified"))
      (node (ref "C111") (pin "1") (pinfunction "1_1") (pintype "unspecified"))
      (node (ref "C112") (pin "1") (pinfunction "1_1") (pintype "unspecified"))
      (node (ref "C113") (pin "1") (pinfunction "1_1") (pintype "input"))
      (node (ref "C114") (pin "1") (pinfunction "1_1") (pintype "input"))
      (node (ref "C27") (pin "1") (pinfunction "1_1") (pintype "input"))
      (node (ref "C28") (pin "2") (pinfunction "2_2") (pintype "input"))
      (node (ref "C40") (pin "1") (pinfunction "1_1") (pintype "input"))
      (node (ref "C41") (pin "2") (pinfunction "2_2") (pintype "input"))
      (node (ref "C73") (pin "1") (pinfunction "1_1") (pintype "unspecified"))
      (node (ref "C74") (pin "1") (pinfunction "1_1") (pintype "unspecified"))
      (node (ref "C75") (pin "1") (pinfunction "1_1") (pintype "unspecified"))
      (node (ref "C76") (pin "1") (pinfunction "1_1") (pintype "input"))
      (node (ref "C77") (pin "1") (pinfunction "1_1") (pintype "input"))
      (node (ref "C79") (pin "1") (pinfunction "1_1") (pintype "input"))
      (node (ref "C80") (pin "1") (pinfunction "1_1") (pintype "unspecified"))
      (node (ref "C81") (pin "1") (pinfunction "1_1") (pintype "unspecified"))
      (node (ref "C82") (pin "1") (pinfunction "1_1") (pintype "unspecified"))
      (node (ref "C83") (pin "1") (pinfunction "1_1") (pintype "input"))
      (node (ref "R19") (pin "1") (pinfunction "1_1") (pintype "unspecified"))
      (node (ref "R20") (pin "1") (pinfunction "1_1") (pintype "unspecified"))
      (node (ref "U1") (pin "33") (pinfunction "VDD_33") (pintype "unspecified"))
      (node (ref "U10") (pin "33") (pinfunction "VDD_33") (pintype "unspecified"))
    )
    (net (code "104") (name "VIN") (class "Default")
      (node (ref "H1") (pin "1") (pinfunction "1_1") (pintype "unspecified"))
      (node (ref "U8") (pin "1") (pinfunction "IN+_1") (pintype "unspecified"))
      (node (ref "U8") (pin "12") (pinfunction "VBUS_12") (pintype "unspecified"))
    )
    (net (code "105") (name "VIN_M") (class "Default")
      (node (ref "H1") (pin "2") (pinfunction "2_2") (pintype "unspecified"))
    )
    (net (code "106") (name "VOUT") (class "Default")
      (node (ref "C23") (pin "1") (pinfunction "1_1") (pintype "input"))
      (node (ref "C24") (pin "1") (pinfunction "1_1") (pintype "input"))
      (node (ref "L1") (pin "2") (pinfunction "2_2") (pintype "unspecified"))
      (node (ref "R10") (pin "1") (pinfunction "1_1") (pintype "unspecified"))
      (node (ref "R12") (pin "2") (pinfunction "2_2") (pintype "input"))
    )
    (net (code "107") (name "XIN32") (class "Default")
      (node (ref "C7") (pin "2") (pinfunction "2_2") (pintype "unspecified"))
      (node (ref "U4") (pin "8") (pinfunction "IO15_8") (pintype "unspecified"))
      (node (ref "X1") (pin "1") (pinfunction "1_1") (pintype "unspecified"))
    )
    (net (code "108") (name "XOUT32") (class "Default")
      (node (ref "C6") (pin "2") (pinfunction "2_2") (pintype "unspecified"))
      (node (ref "U4") (pin "9") (pinfunction "IO16_9") (pintype "unspecified"))
      (node (ref "X1") (pin "2") (pinfunction "2_2") (pintype "unspecified"))
    )
    (net (code "109") (name "unconnected-(Q1-D-Pad6)") (class "Default")
      (node (ref "Q1") (pin "6") (pinfunction "D_6") (pintype "unspecified"))
    )
    (net (code "110") (name "unconnected-(Q1-D-Pad7)") (class "Default")
      (node (ref "Q1") (pin "7") (pinfunction "D_7") (pintype "unspecified"))
    )
    (net (code "111") (name "unconnected-(Q1-D-Pad8)") (class "Default")
      (node (ref "Q1") (pin "8") (pinfunction "D_8") (pintype "unspecified"))
    )
    (net (code "112") (name "unconnected-(Q1-D-Pad9)") (class "Default")
      (node (ref "Q1") (pin "9") (pinfunction "D_9") (pintype "unspecified"))
    )
    (net (code "113") (name "unconnected-(Q1-S-Pad1)") (class "Default")
      (node (ref "Q1") (pin "1") (pinfunction "S_1") (pintype "unspecified"))
    )
    (net (code "114") (name "unconnected-(Q1-S-Pad2)") (class "Default")
      (node (ref "Q1") (pin "2") (pinfunction "S_2") (pintype "unspecified"))
    )
    (net (code "115") (name "unconnected-(Q2-D-Pad6)") (class "Default")
      (node (ref "Q2") (pin "6") (pinfunction "D_6") (pintype "unspecified"))
    )
    (net (code "116") (name "unconnected-(Q2-D-Pad7)") (class "Default")
      (node (ref "Q2") (pin "7") (pinfunction "D_7") (pintype "unspecified"))
    )
    (net (code "117") (name "unconnected-(Q2-D-Pad8)") (class "Default")
      (node (ref "Q2") (pin "8") (pinfunction "D_8") (pintype "unspecified"))
    )
    (net (code "118") (name "unconnected-(Q2-D-Pad9)") (class "Default")
      (node (ref "Q2") (pin "9") (pinfunction "D_9") (pintype "unspecified"))
    )
    (net (code "119") (name "unconnected-(Q2-S-Pad1)") (class "Default")
      (node (ref "Q2") (pin "1") (pinfunction "S_1") (pintype "unspecified"))
    )
    (net (code "120") (name "unconnected-(Q2-S-Pad2)") (class "Default")
      (node (ref "Q2") (pin "2") (pinfunction "S_2") (pintype "unspecified"))
    )
    (net (code "121") (name "unconnected-(U1-RF-Pad23)") (class "Default")
      (node (ref "U1") (pin "23") (pinfunction "RF_23") (pintype "unspecified"))
    )
    (net (code "122") (name "unconnected-(U1-TEMP_N-Pad21)") (class "Default")
      (node (ref "U1") (pin "21") (pinfunction "TEMP_N_21") (pintype "unspecified"))
    )
    (net (code "123") (name "unconnected-(U1-TEMP_P-Pad22)") (class "Default")
      (node (ref "U1") (pin "22") (pinfunction "TEMP_P_22") (pintype "unspecified"))
    )
    (net (code "124") (name "unconnected-(U1-TEST-Pad7)") (class "Default")
      (node (ref "U1") (pin "7") (pinfunction "TEST_7") (pintype "unspecified"))
    )
    (net (code "125") (name "unconnected-(U1-TF-Pad24)") (class "Default")
      (node (ref "U1") (pin "24") (pinfunction "TF_24") (pintype "unspecified"))
    )
    (net (code "126") (name "unconnected-(U3-EP-Pad15)") (class "Default")
      (node (ref "U3") (pin "15") (pinfunction "EP_15") (pintype "unspecified"))
    )
    (net (code "127") (name "unconnected-(U3-NC-Pad6)") (class "Default")
      (node (ref "U3") (pin "6") (pinfunction "NC_6") (pintype "unspecified+no_connect"))
    )
    (net (code "128") (name "unconnected-(U3-NC-Pad9)") (class "Default")
      (node (ref "U3") (pin "9") (pinfunction "NC_9") (pintype "unspecified+no_connect"))
    )
    (net (code "129") (name "unconnected-(U4-GND-Pad40)") (class "Default")
      (node (ref "U4") (pin "40") (pinfunction "GND_40") (pintype "unspecified"))
    )
    (net (code "130") (name "unconnected-(U4-GND-Pad41)") (class "Default")
      (node (ref "U4") (pin "41") (pinfunction "GND_41") (pintype "unspecified"))
    )
    (net (code "131") (name "unconnected-(U4-IO0-Pad27)") (class "Default")
      (node (ref "U4") (pin "27") (pinfunction "IO0_27") (pintype "unspecified"))
    )
    (net (code "132") (name "unconnected-(U4-IO3-Pad15)") (class "Default")
      (node (ref "U4") (pin "15") (pinfunction "IO3_15") (pintype "unspecified"))
    )
    (net (code "133") (name "unconnected-(U4-IO4-Pad4)") (class "Default")
      (node (ref "U4") (pin "4") (pinfunction "IO4_4") (pintype "unspecified"))
    )
    (net (code "134") (name "unconnected-(U4-IO8-Pad12)") (class "Default")
      (node (ref "U4") (pin "12") (pinfunction "IO8_12") (pintype "unspecified"))
    )
    (net (code "135") (name "unconnected-(U4-IO9-Pad17)") (class "Default")
      (node (ref "U4") (pin "17") (pinfunction "IO9_17") (pintype "unspecified"))
    )
    (net (code "136") (name "unconnected-(U4-IO11-Pad19)") (class "Default")
      (node (ref "U4") (pin "19") (pinfunction "IO11_19") (pintype "unspecified"))
    )
    (net (code "137") (name "unconnected-(U4-IO13-Pad21)") (class "Default")
      (node (ref "U4") (pin "21") (pinfunction "IO13_21") (pintype "unspecified"))
    )
    (net (code "138") (name "unconnected-(U4-IO14-Pad22)") (class "Default")
      (node (ref "U4") (pin "22") (pinfunction "IO14_22") (pintype "unspecified"))
    )
    (net (code "139") (name "unconnected-(U4-IO20-Pad14)") (class "Default")
      (node (ref "U4") (pin "14") (pinfunction "IO20_14") (pintype "unspecified"))
    )
    (net (code "140") (name "unconnected-(U4-IO21-Pad23)") (class "Default")
      (node (ref "U4") (pin "23") (pinfunction "IO21_23") (pintype "unspecified"))
    )
    (net (code "141") (name "unconnected-(U4-IO38-Pad31)") (class "Default")
      (node (ref "U4") (pin "31") (pinfunction "IO38_31") (pintype "unspecified"))
    )
    (net (code "142") (name "unconnected-(U4-IO45-Pad26)") (class "Default")
      (node (ref "U4") (pin "26") (pinfunction "IO45_26") (pintype "unspecified"))
    )
    (net (code "143") (name "unconnected-(U4-IO46-Pad16)") (class "Default")
      (node (ref "U4") (pin "16") (pinfunction "IO46_16") (pintype "unspecified"))
    )
    (net (code "144") (name "unconnected-(U5-NC-Pad4)") (class "Default")
      (node (ref "U5") (pin "4") (pinfunction "NC_4") (pintype "unspecified"))
    )
    (net (code "145") (name "unconnected-(U6-ENSS-Pad2)") (class "Default")
      (node (ref "U6") (pin "2") (pinfunction "ENSS_2") (pintype "unspecified"))
    )
    (net (code "146") (name "unconnected-(U7-FS1-Pad3)") (class "Default")
      (node (ref "U7") (pin "3") (pinfunction "FS1_3") (pintype "unspecified"))
    )
    (net (code "147") (name "unconnected-(U8-ALERT-Pad7)") (class "Default")
      (node (ref "U8") (pin "7") (pinfunction "ALERT_7") (pintype "unspecified"))
    )
    (net (code "148") (name "unconnected-(U8-IN+-Pad2)") (class "Default")
      (node (ref "U8") (pin "2") (pinfunction "IN+_2") (pintype "unspecified"))
    )
    (net (code "149") (name "unconnected-(U8-IN+-Pad3)") (class "Default")
      (node (ref "U8") (pin "3") (pinfunction "IN+_3") (pintype "unspecified"))
    )
    (net (code "150") (name "unconnected-(U8-IN--Pad14)") (class "Default")
      (node (ref "U8") (pin "14") (pinfunction "IN-_14") (pintype "unspecified"))
    )
    (net (code "151") (name "unconnected-(U8-IN--Pad15)") (class "Default")
      (node (ref "U8") (pin "15") (pinfunction "IN-_15") (pintype "unspecified"))
    )
    (net (code "152") (name "unconnected-(U8-IN--Pad16)") (class "Default")
      (node (ref "U8") (pin "16") (pinfunction "IN-_16") (pintype "unspecified"))
    )
    (net (code "153") (name "unconnected-(U8-NC-Pad13)") (class "Default")
      (node (ref "U8") (pin "13") (pinfunction "NC_13") (pintype "unspecified"))
    )
    (net (code "154") (name "unconnected-(U8-SCL-Pad9)") (class "Default")
      (node (ref "U8") (pin "9") (pinfunction "SCL_9") (pintype "unspecified"))
    )
    (net (code "155") (name "unconnected-(U8-SDA-Pad8)") (class "Default")
      (node (ref "U8") (pin "8") (pinfunction "SDA_8") (pintype "unspecified"))
    )
    (net (code "156") (name "unconnected-(U8-VS-Pad10)") (class "Default")
      (node (ref "U8") (pin "10") (pinfunction "VS_10") (pintype "unspecified"))
    )
    (net (code "157") (name "unconnected-(U10-RF-Pad23)") (class "Default")
      (node (ref "U10") (pin "23") (pinfunction "RF_23") (pintype "unspecified"))
    )
    (net (code "158") (name "unconnected-(U10-TEST-Pad7)") (class "Default")
      (node (ref "U10") (pin "7") (pinfunction "TEST_7") (pintype "unspecified"))
    )
    (net (code "159") (name "unconnected-(U10-TF-Pad24)") (class "Default")
      (node (ref "U10") (pin "24") (pinfunction "TF_24") (pintype "unspecified"))
    )
    (net (code "160") (name "unconnected-(X2-Pad5)") (class "Default")
      (node (ref "X2") (pin "5") (pinfunction "5_5") (pintype "unspecified"))
    )
  )
)
